# dw8e.net
KiCad netlist of a schematic drawn in EAGLE
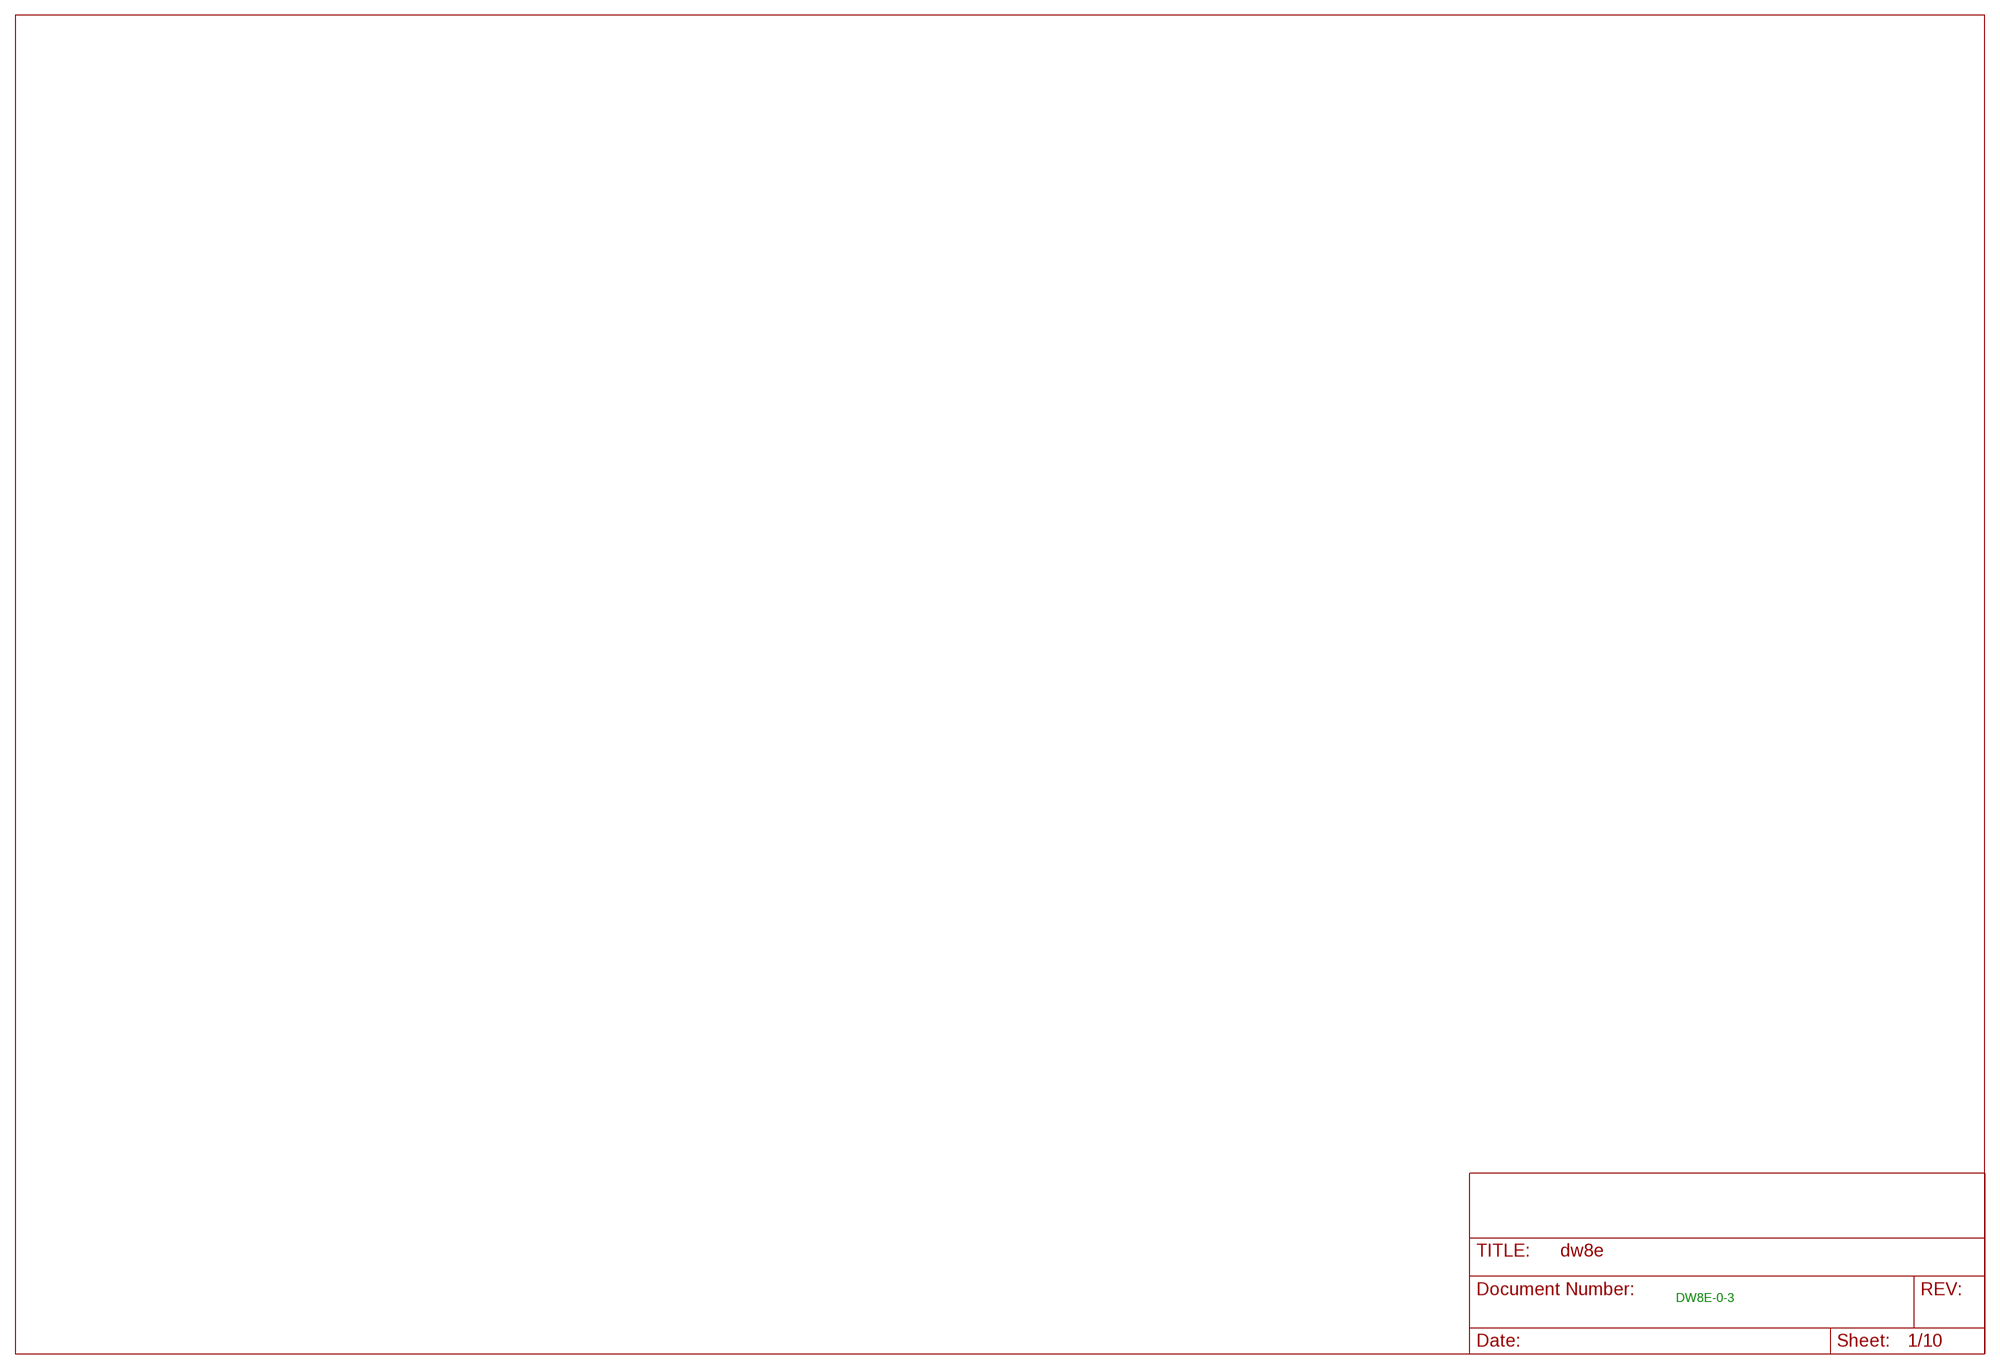
[diagram p0: schematic, sheet 1]
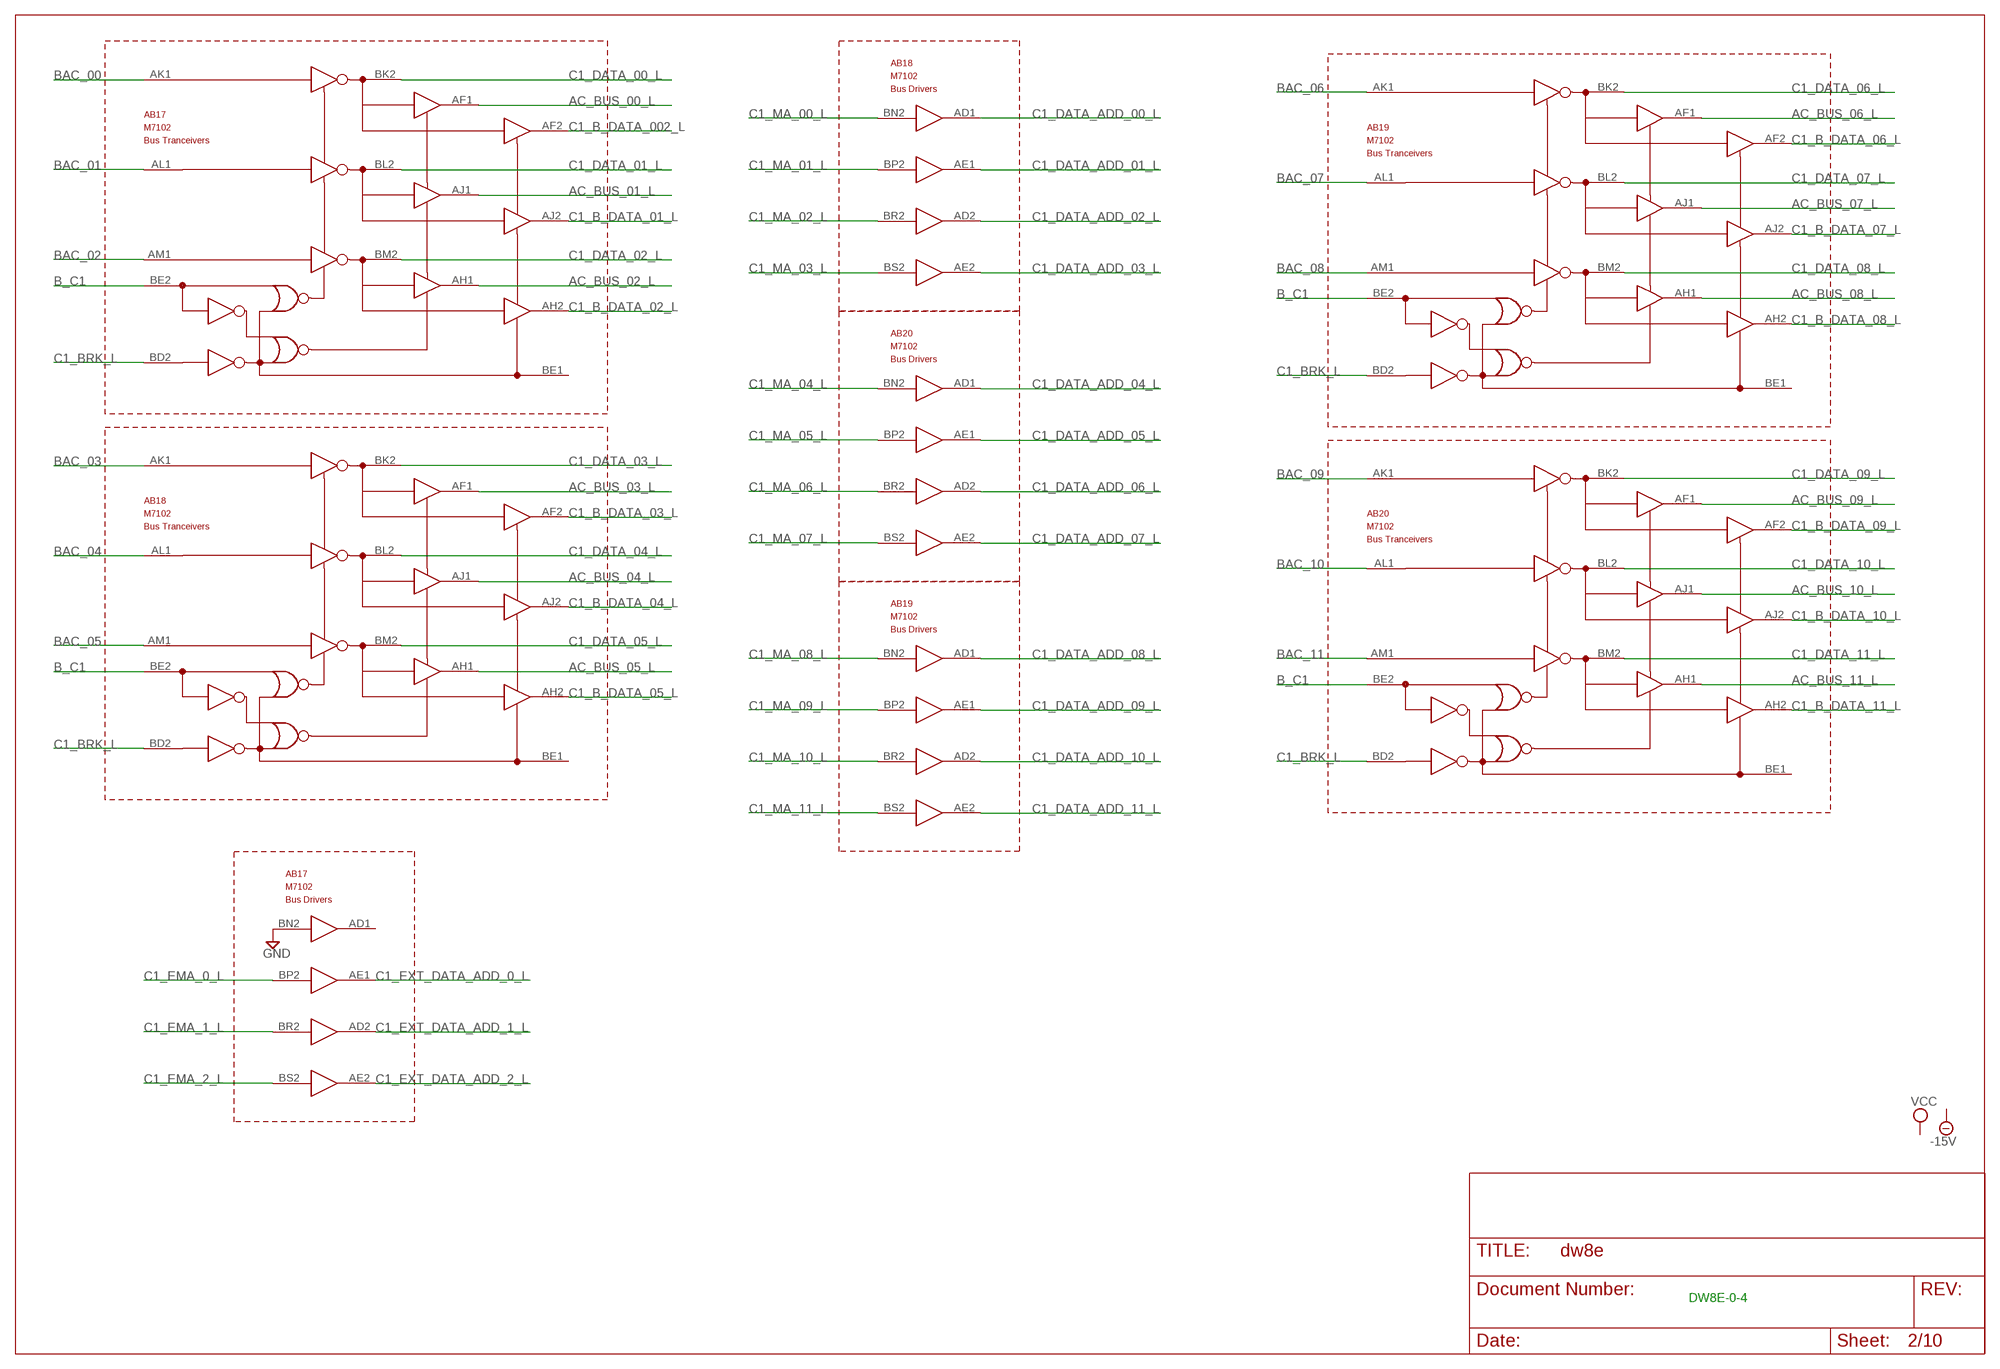
[diagram p1: schematic, sheet 2]
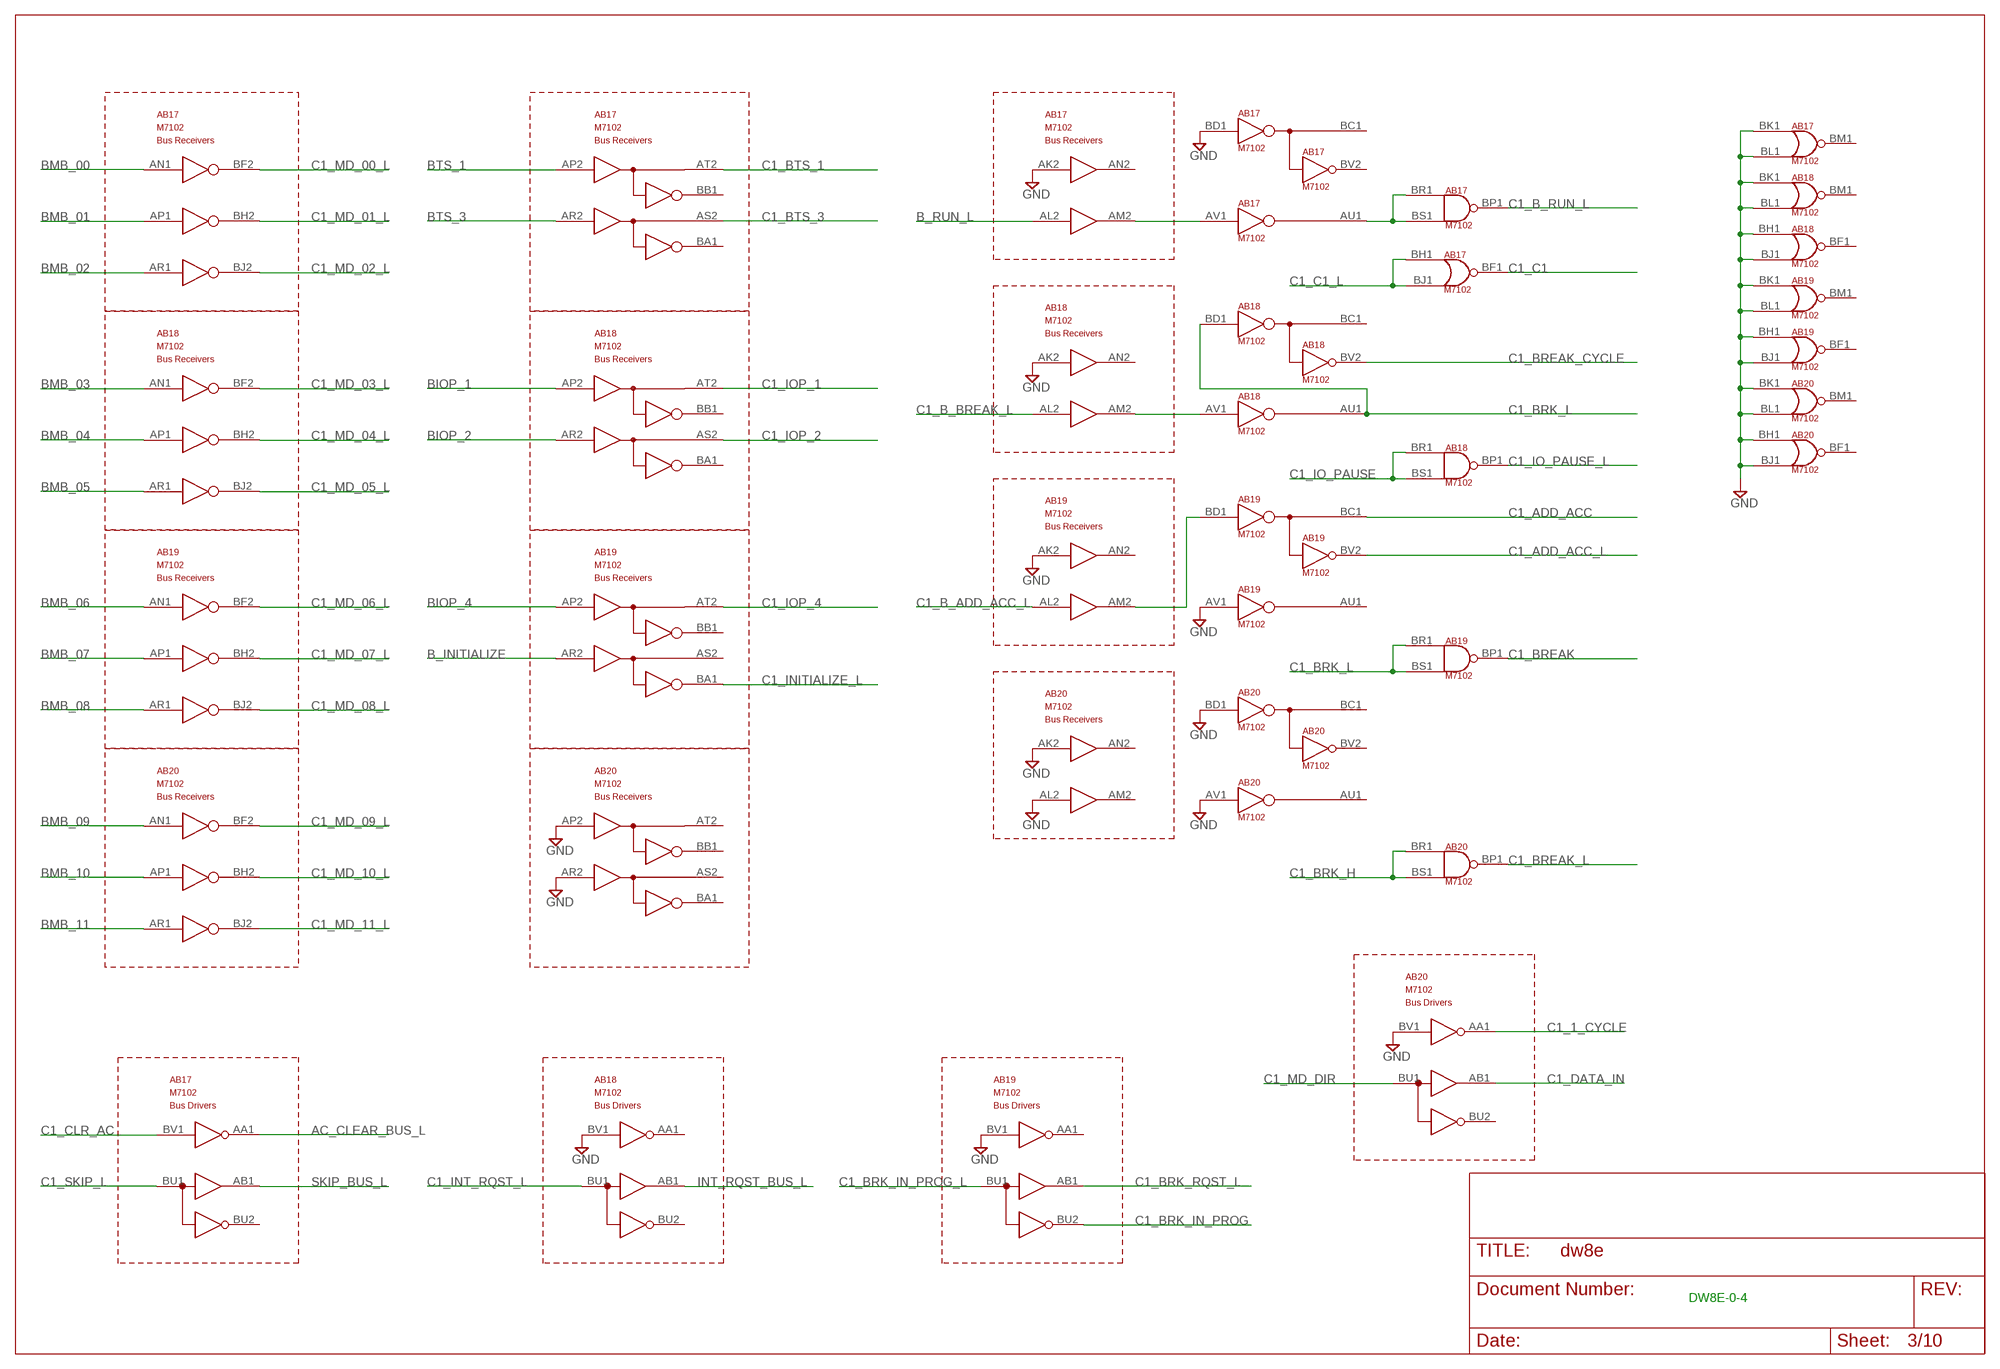
[diagram p2: schematic, sheet 3]
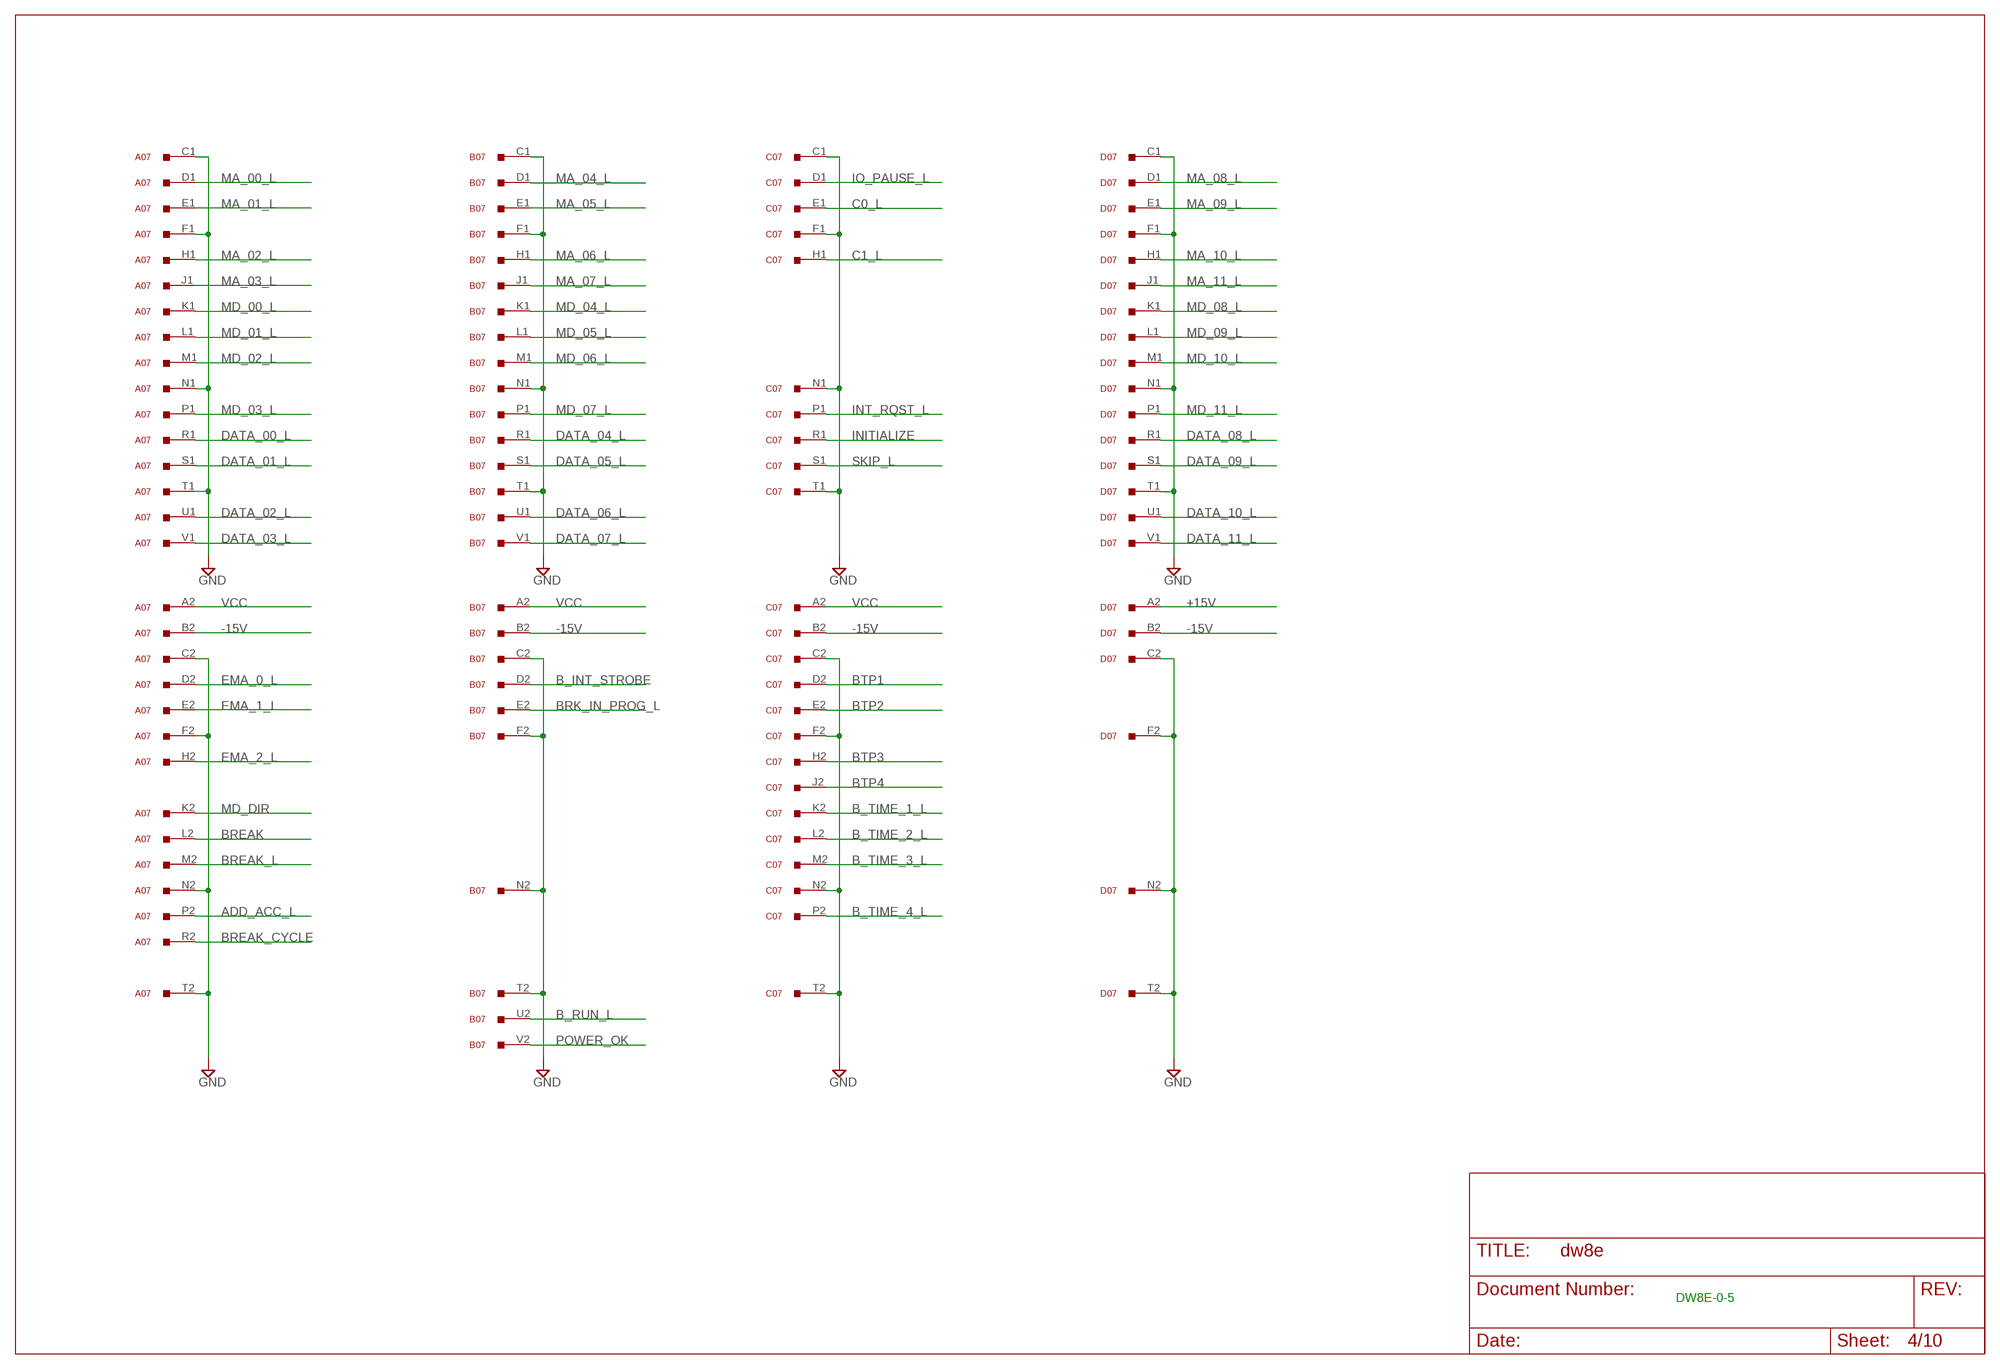
[diagram p3: schematic, sheet 4]
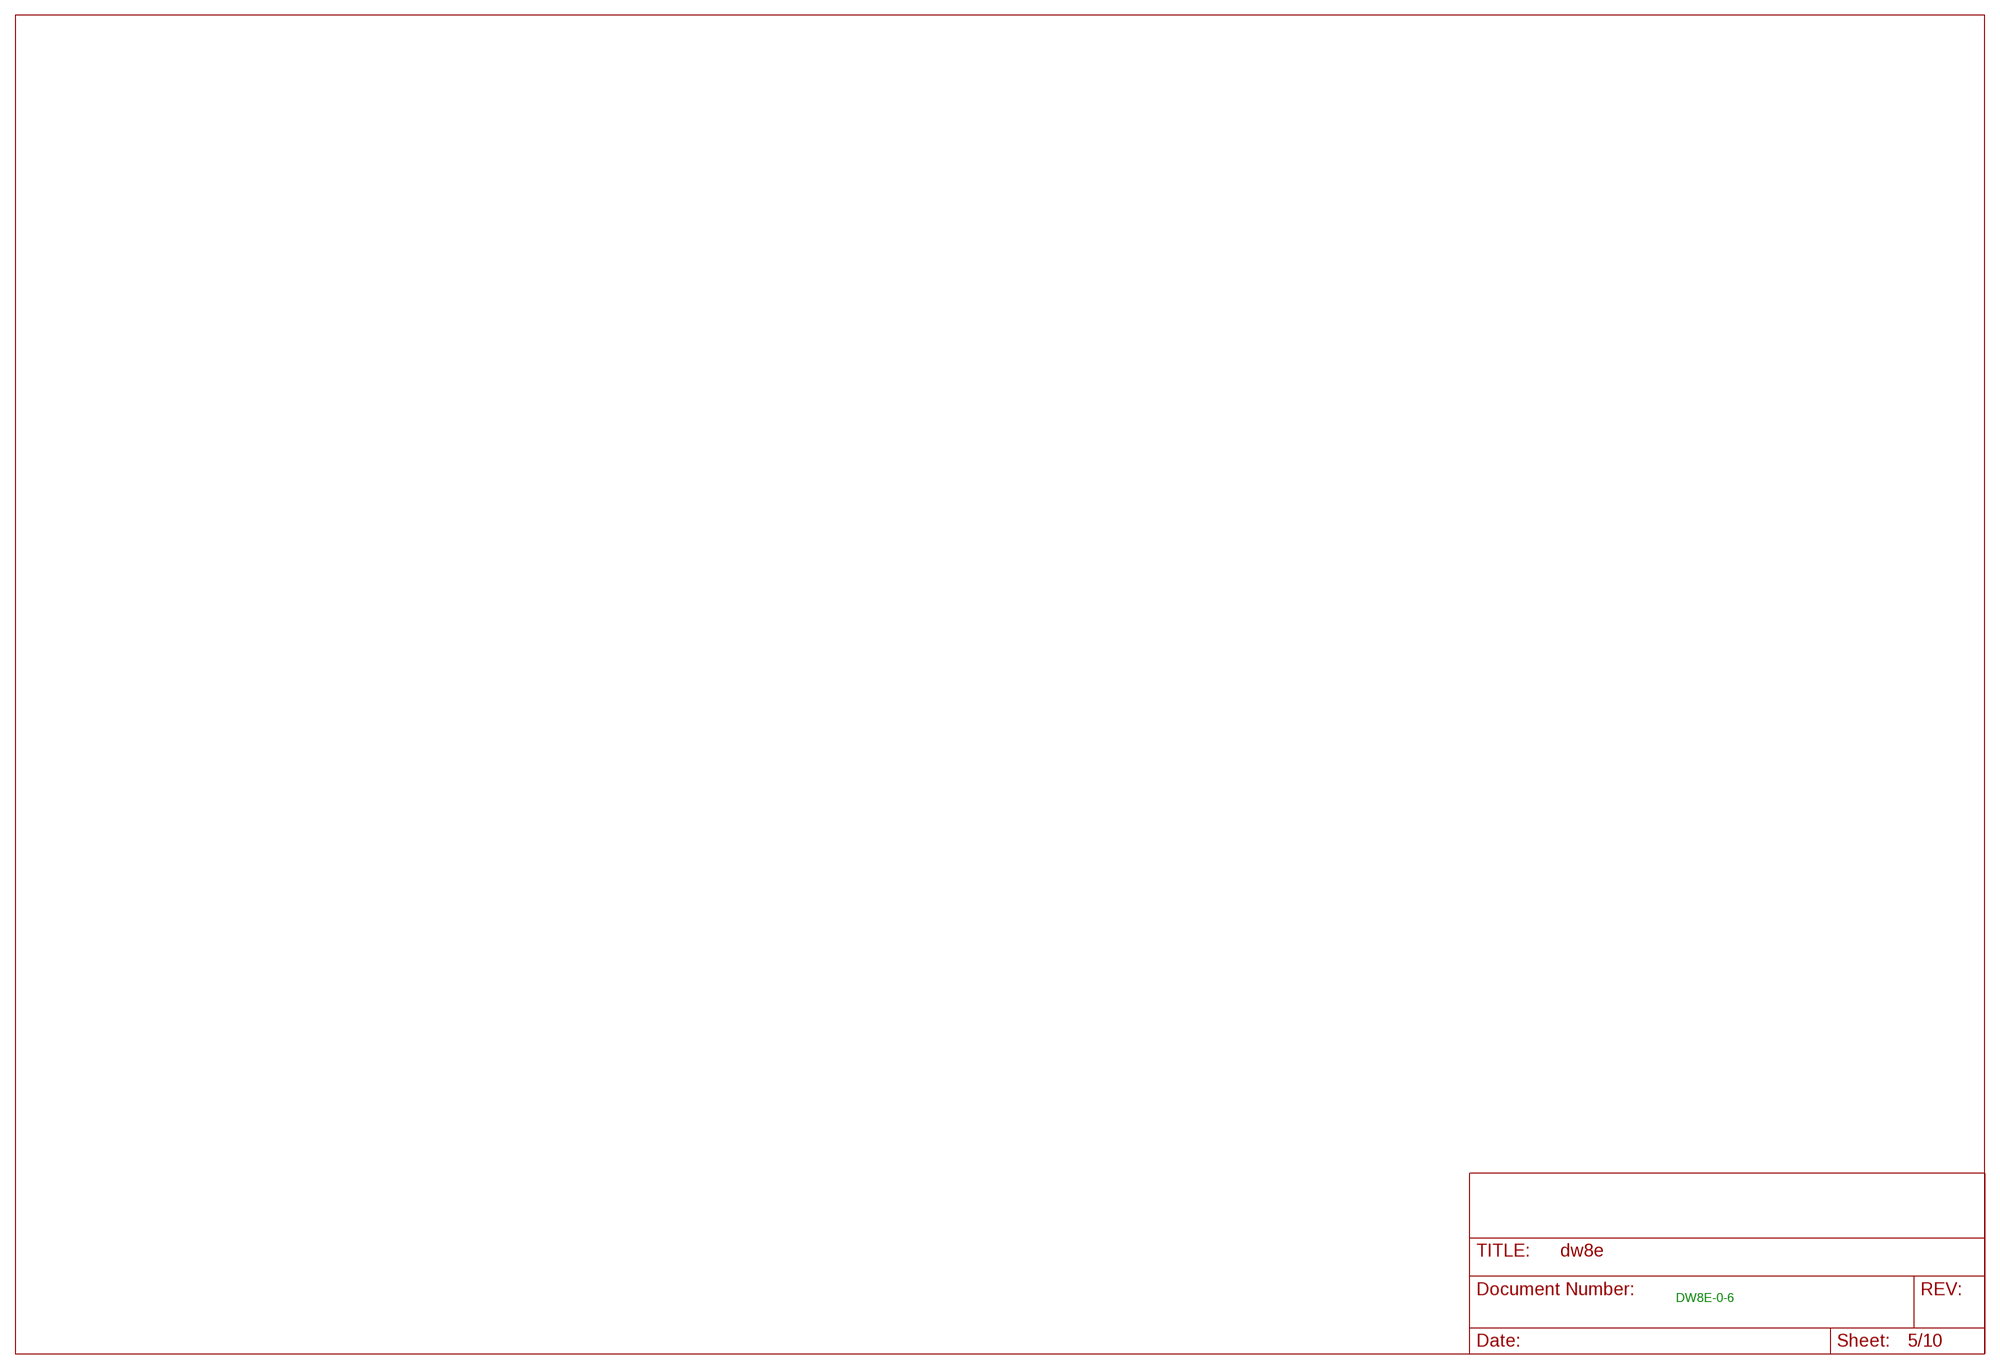
[diagram p4: schematic, sheet 5]
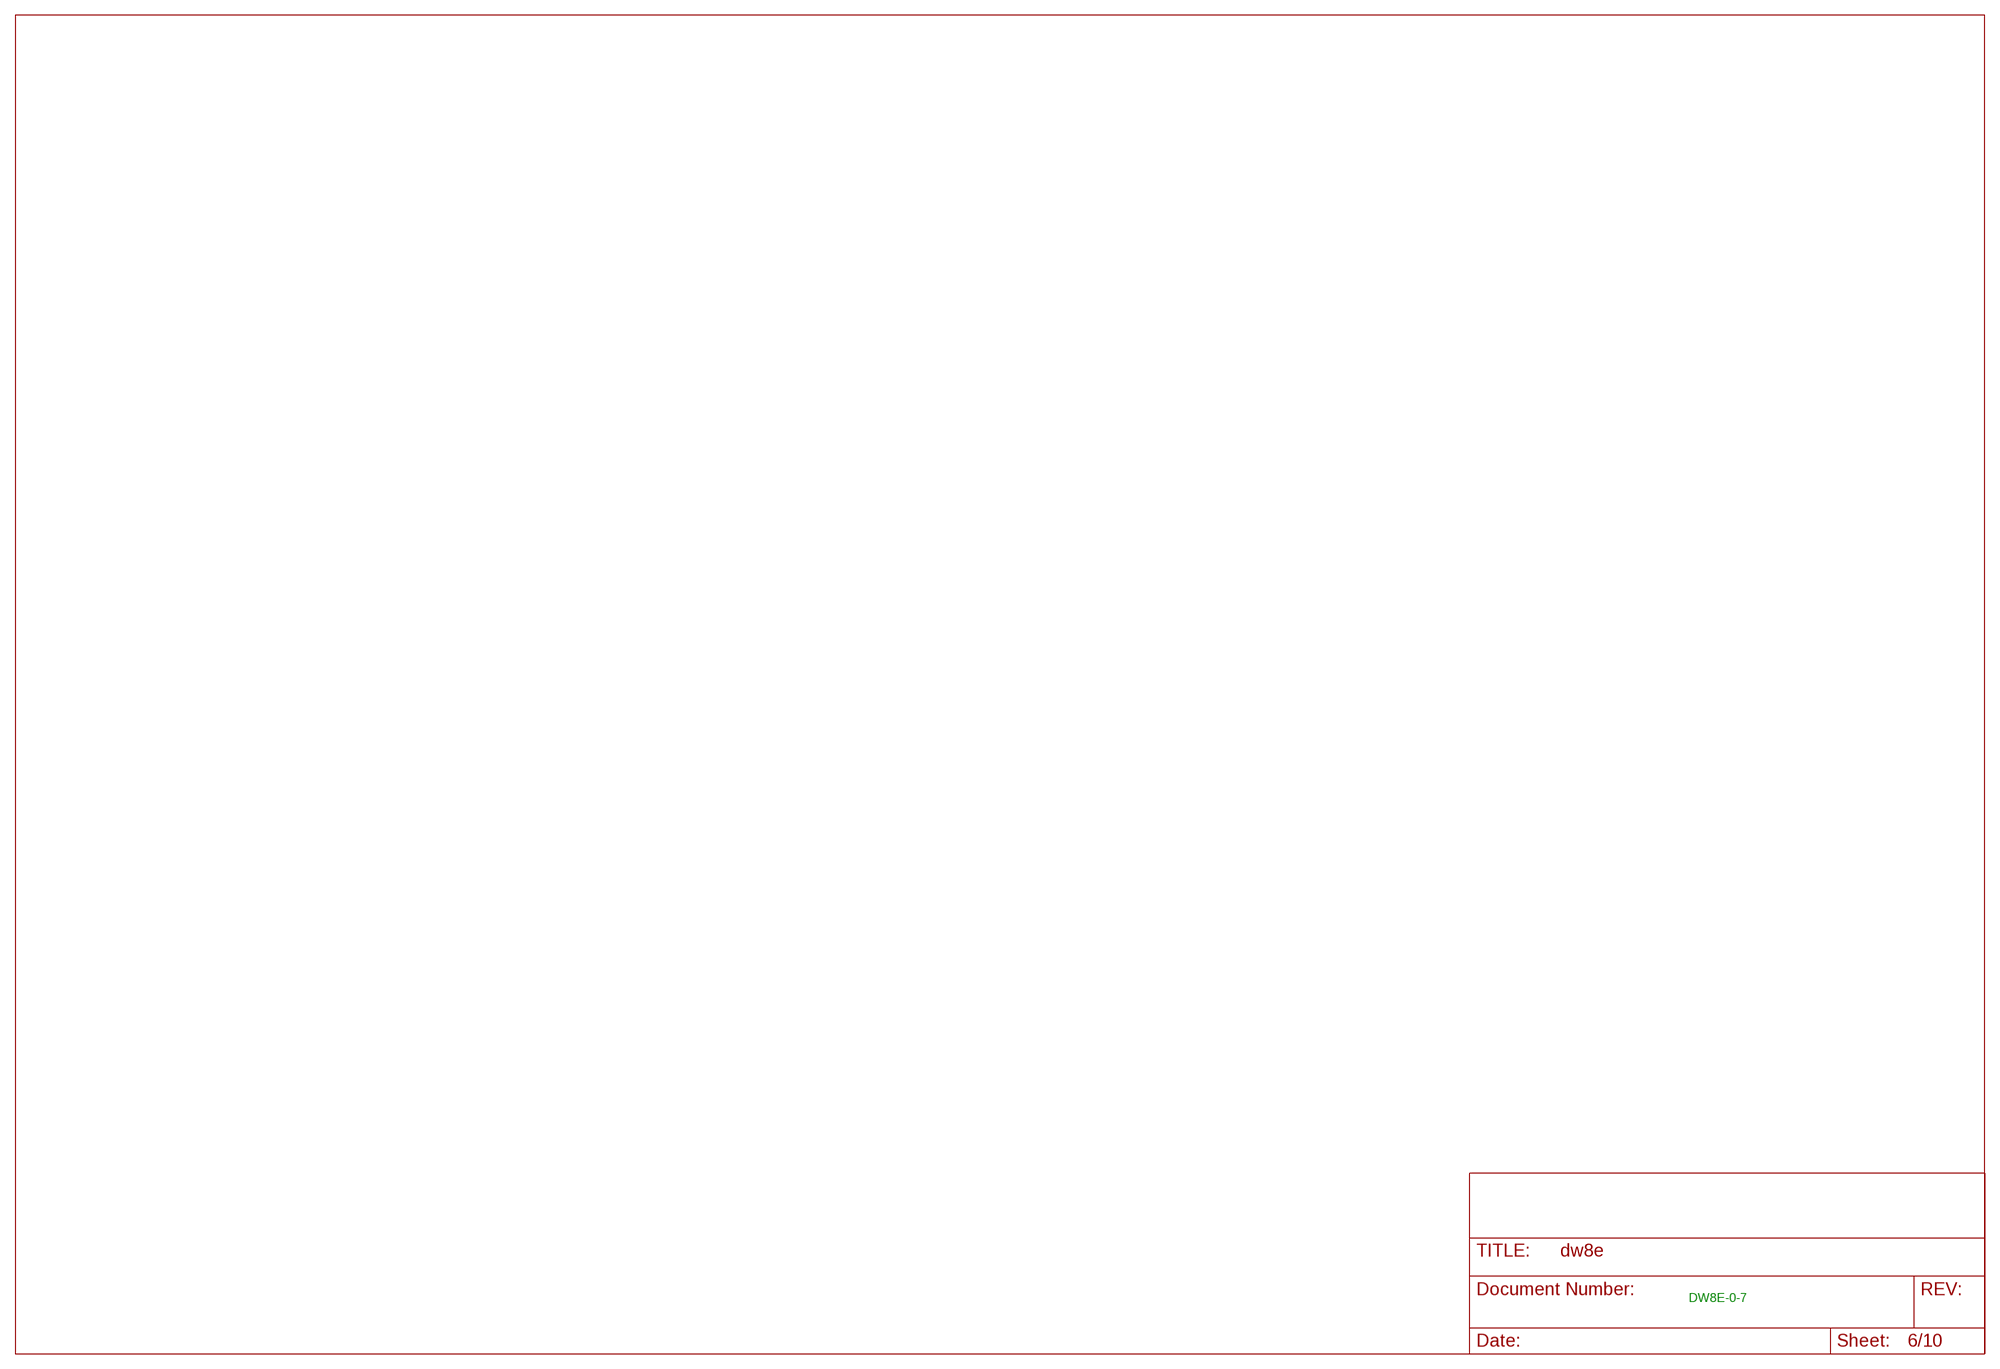
[diagram p5: schematic, sheet 6]
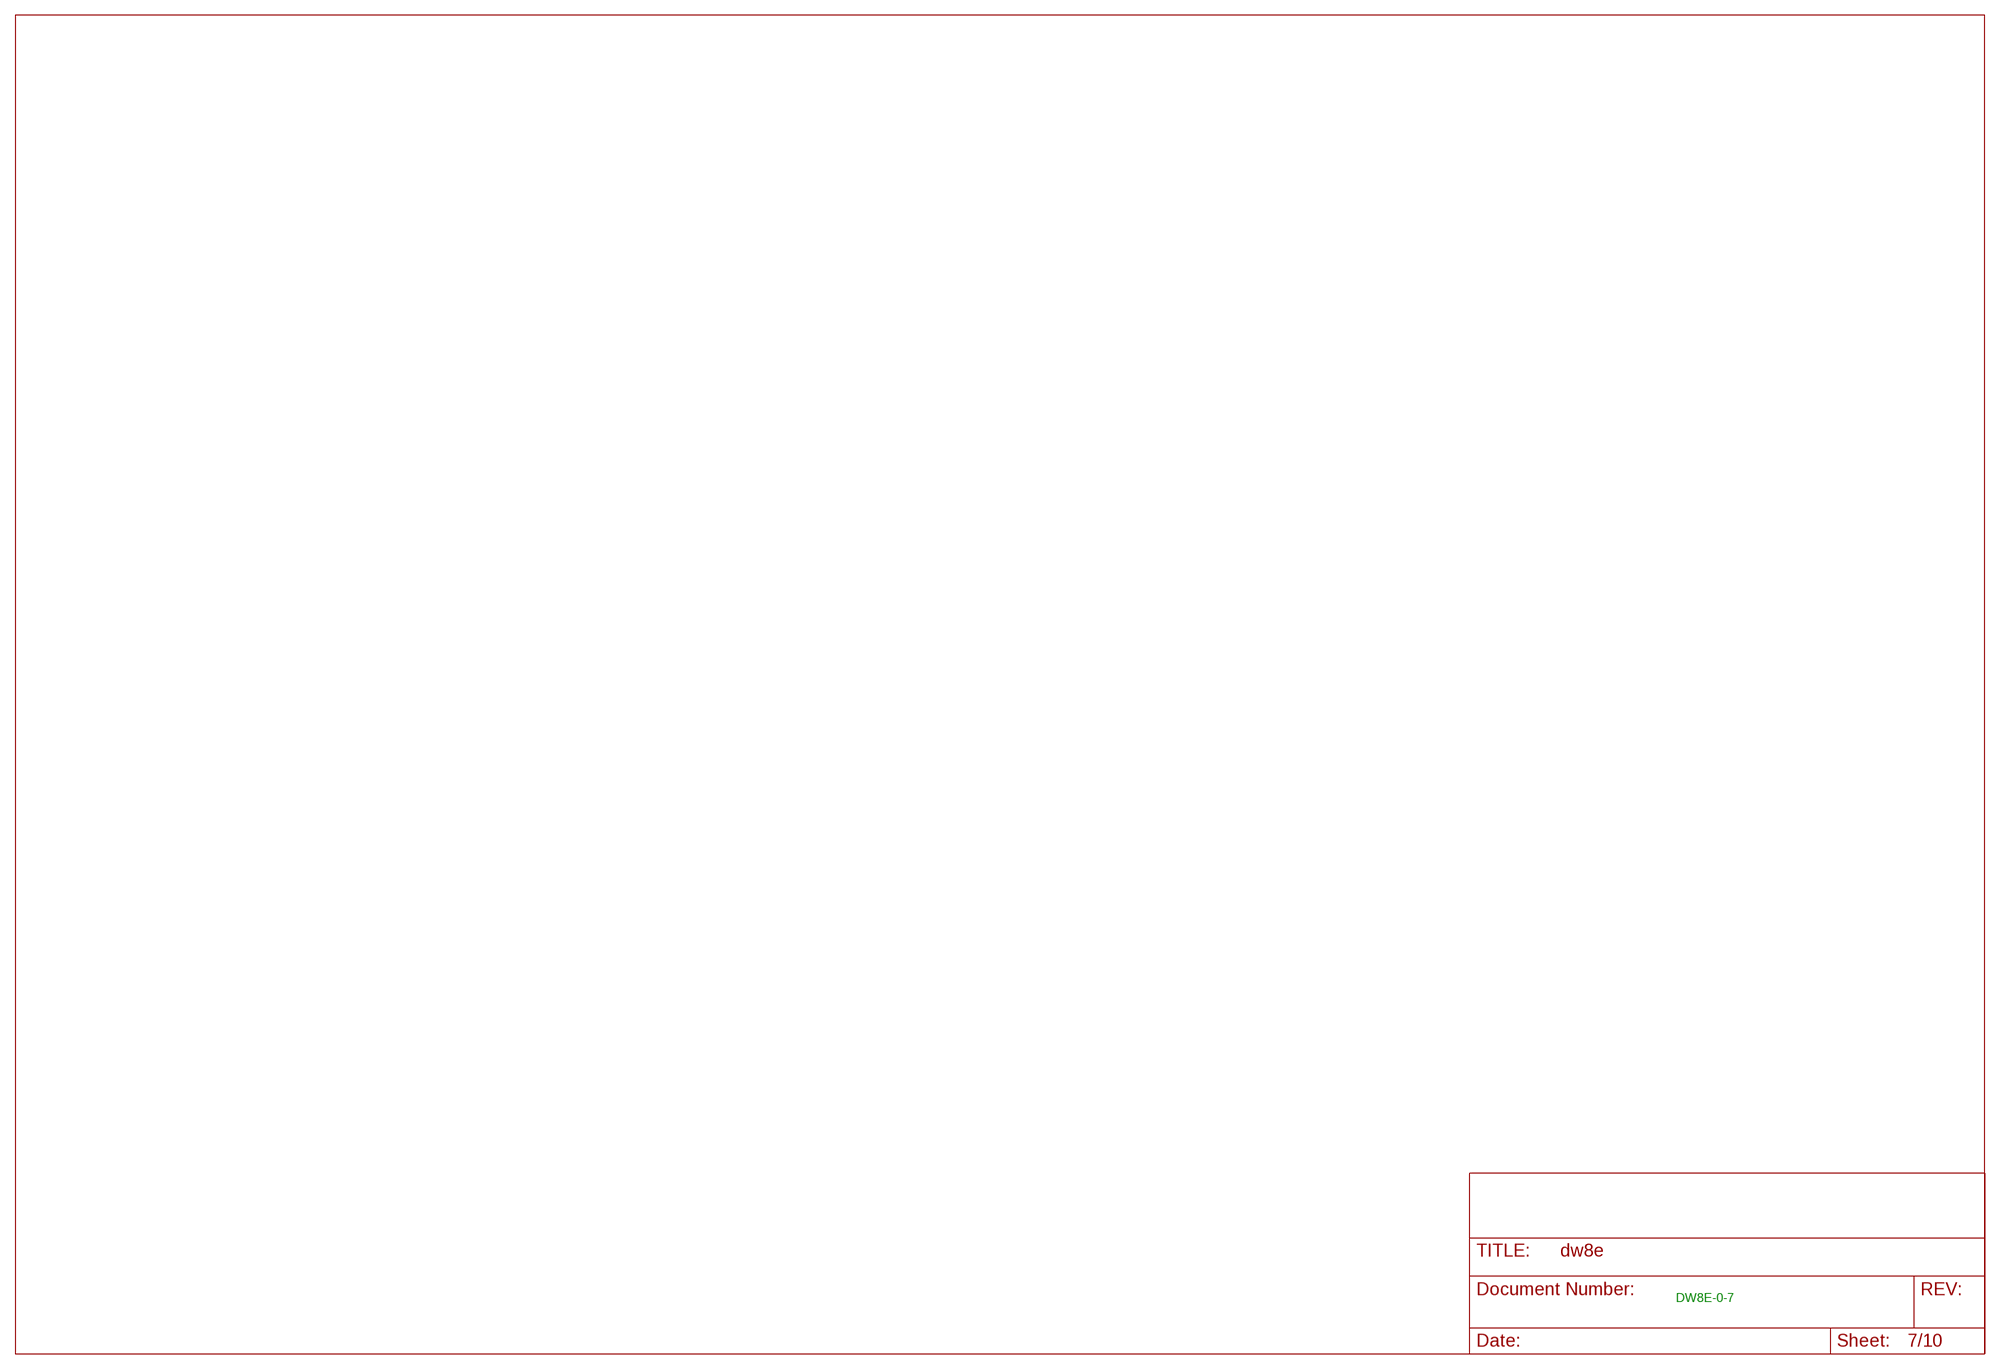
[diagram p6: schematic, sheet 7]
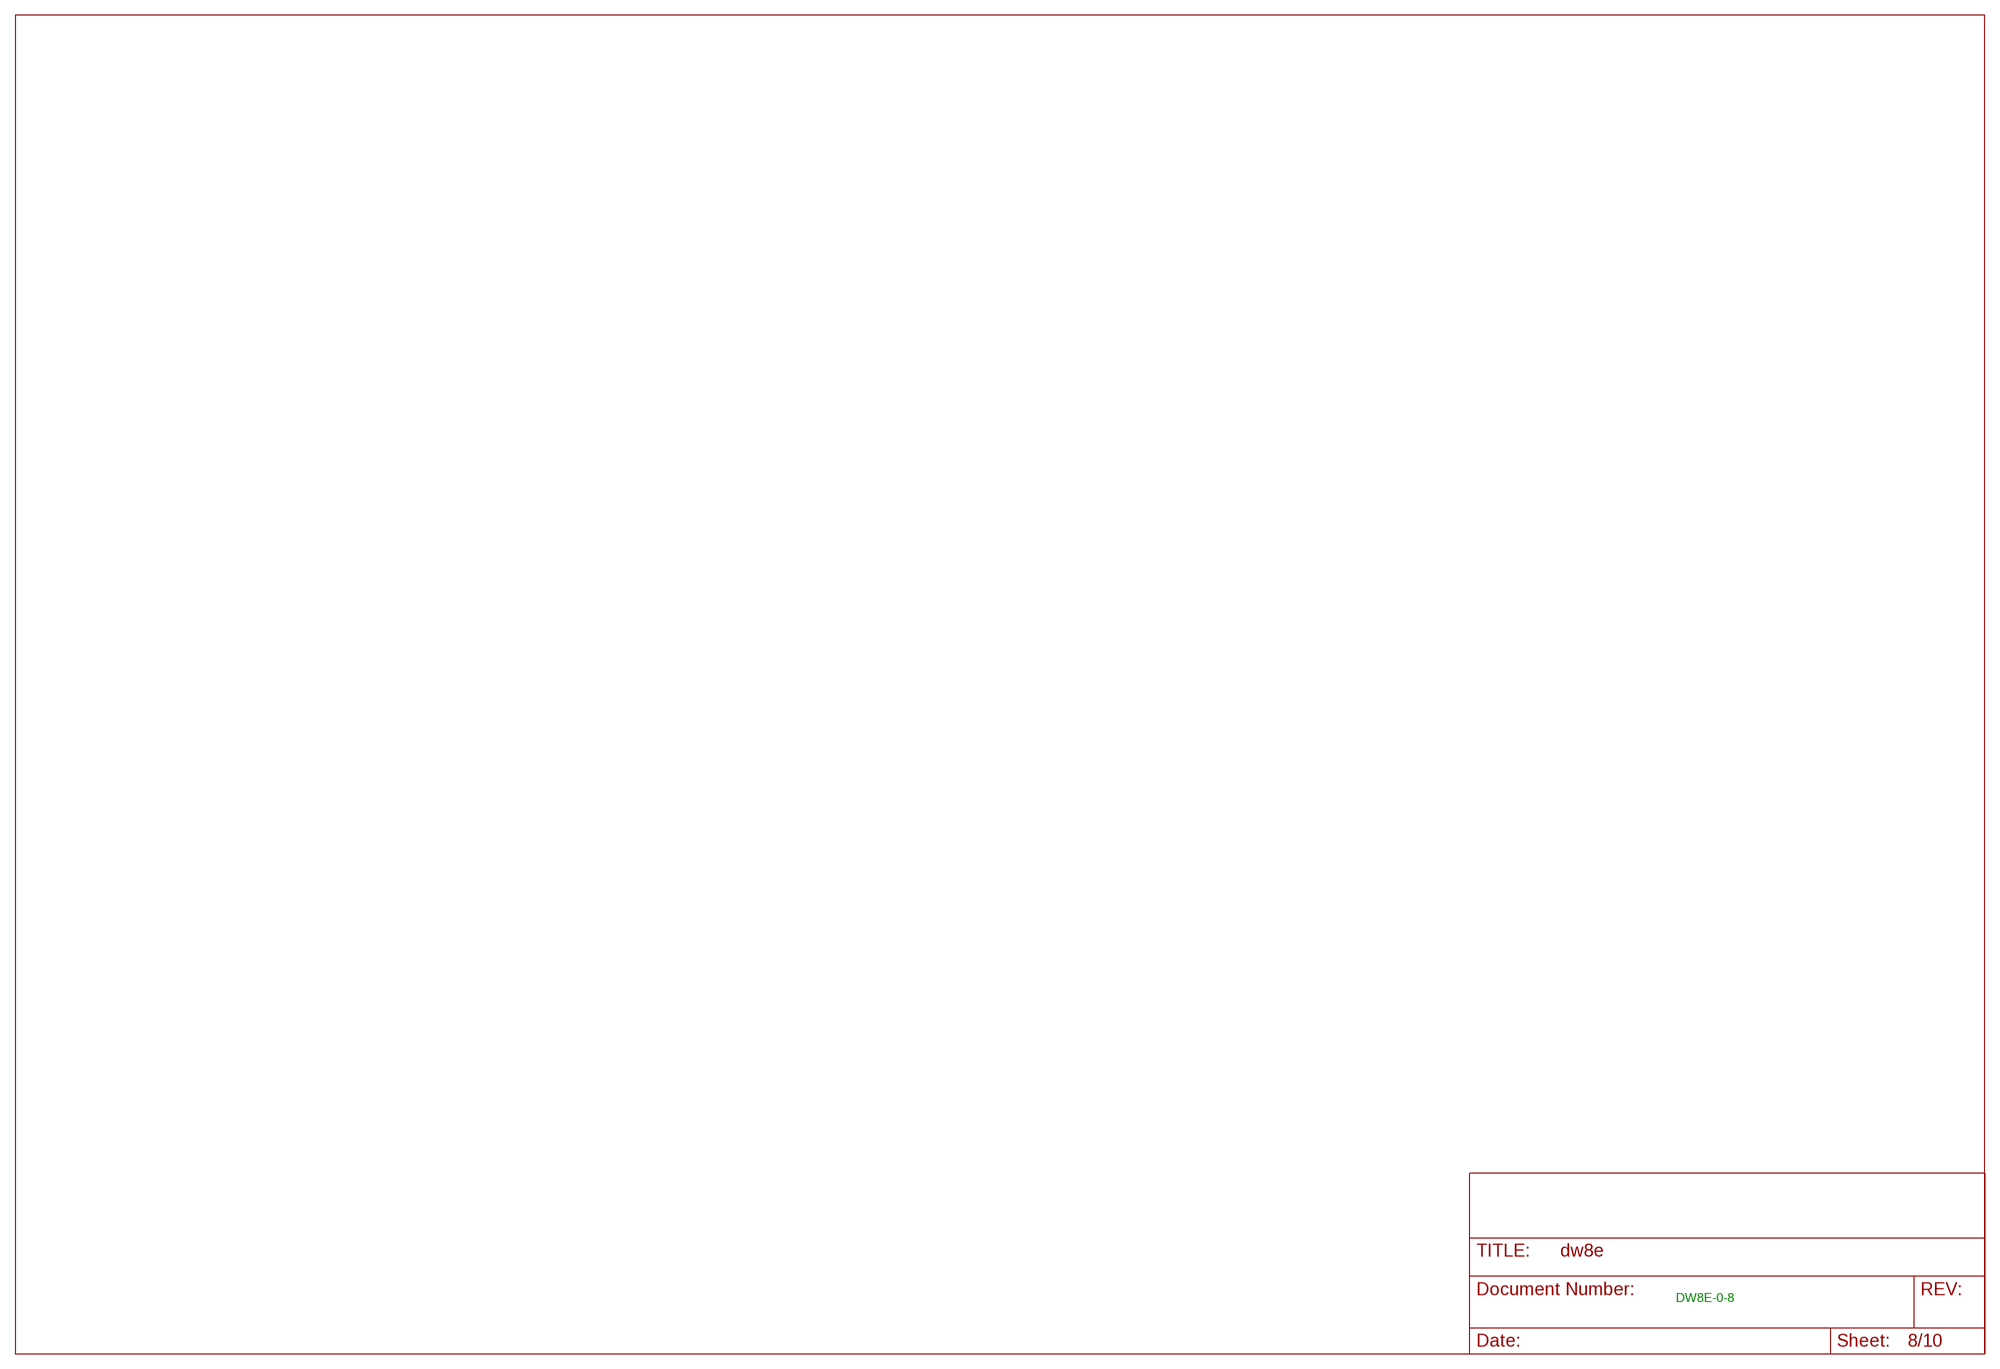
[diagram p7: schematic, sheet 8]
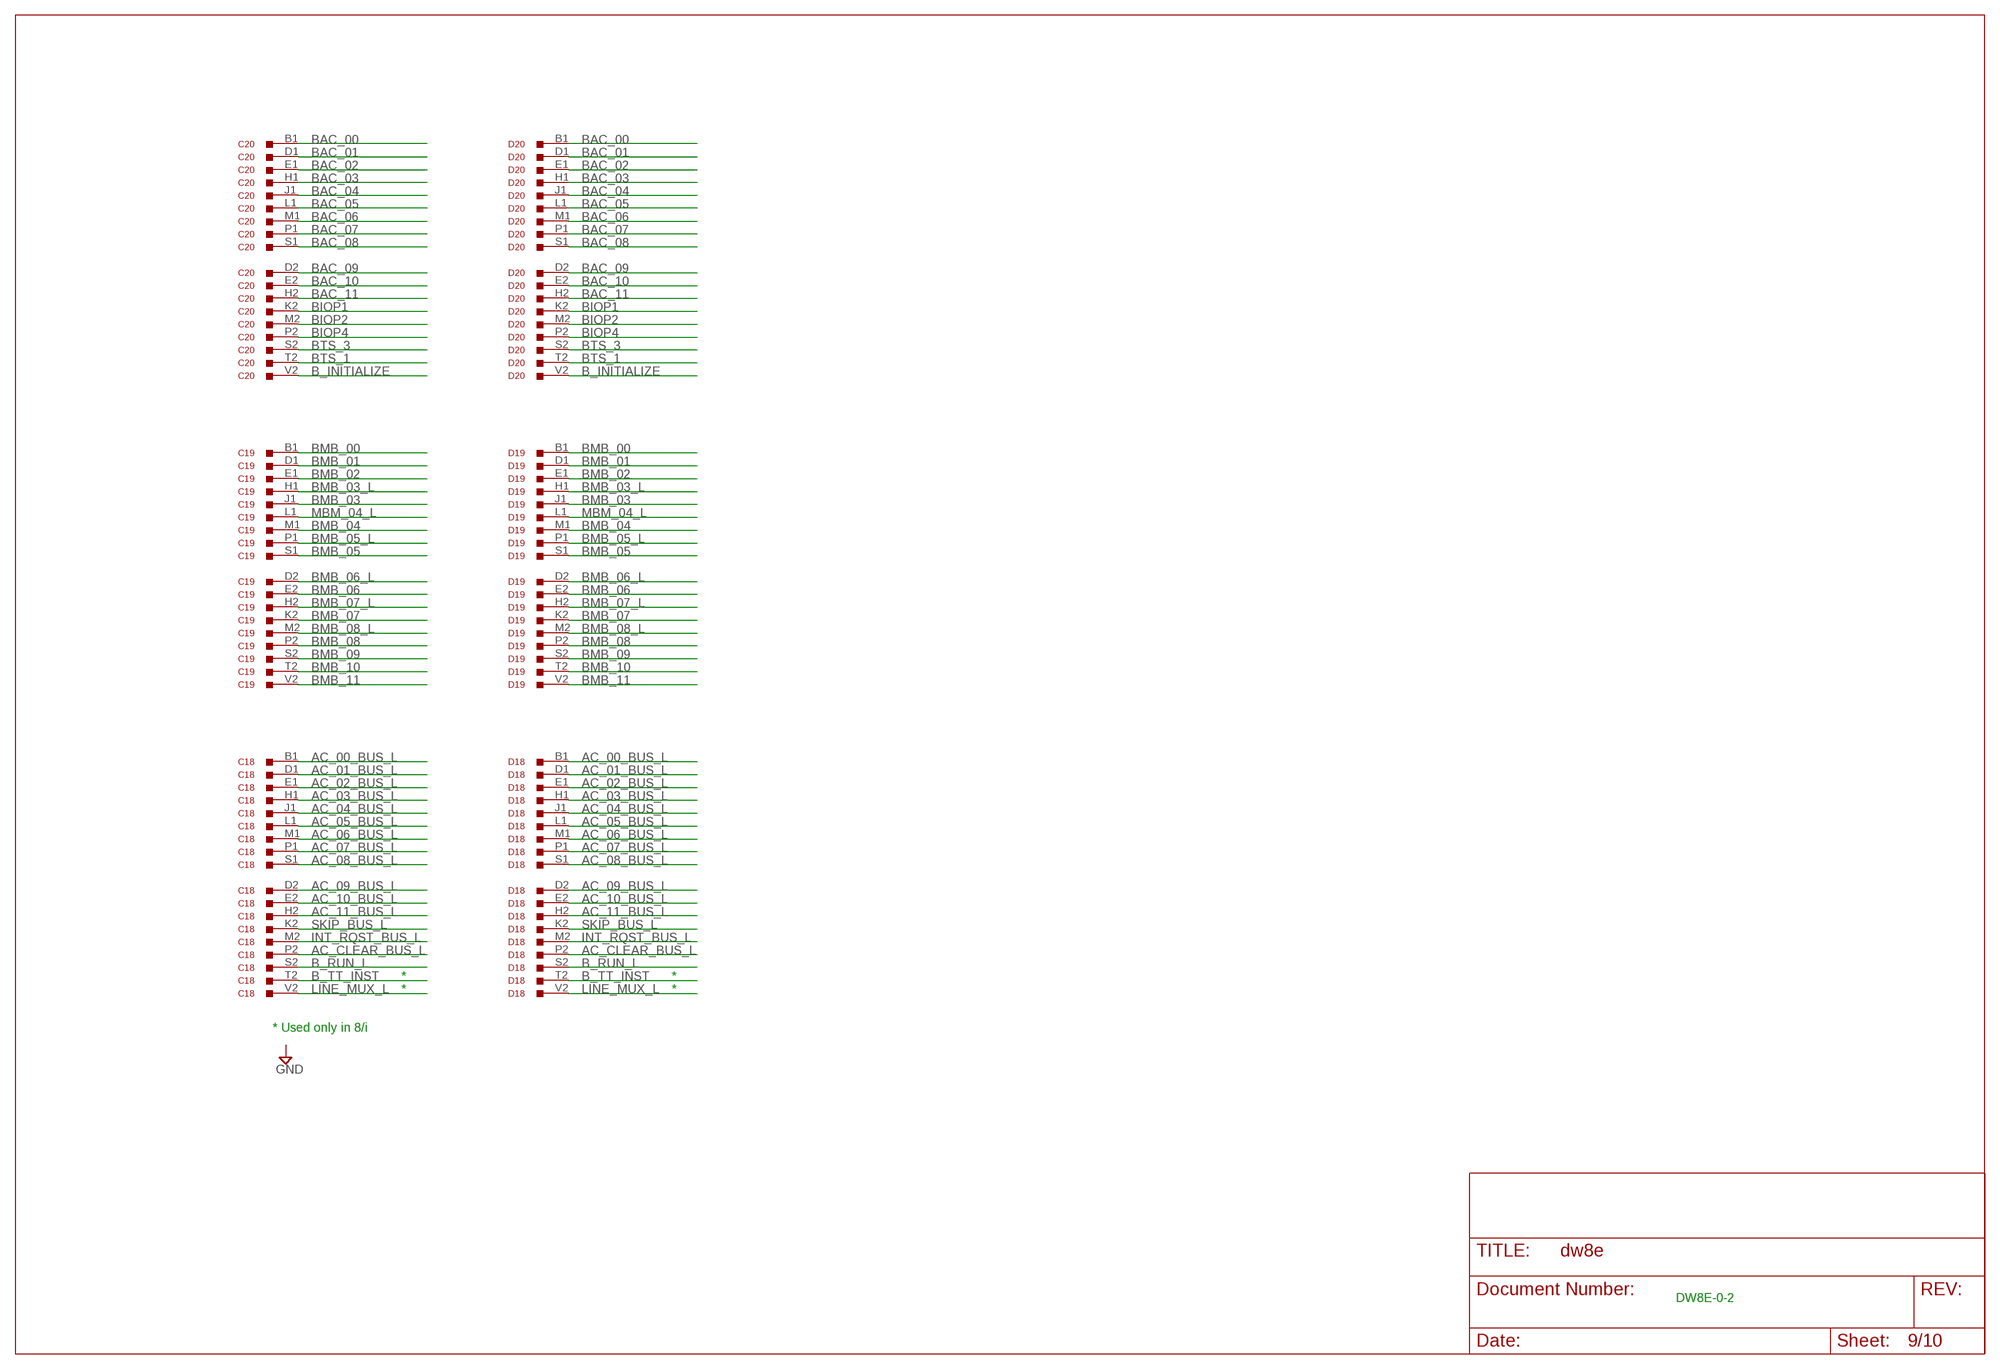
[diagram p8: schematic, sheet 9]
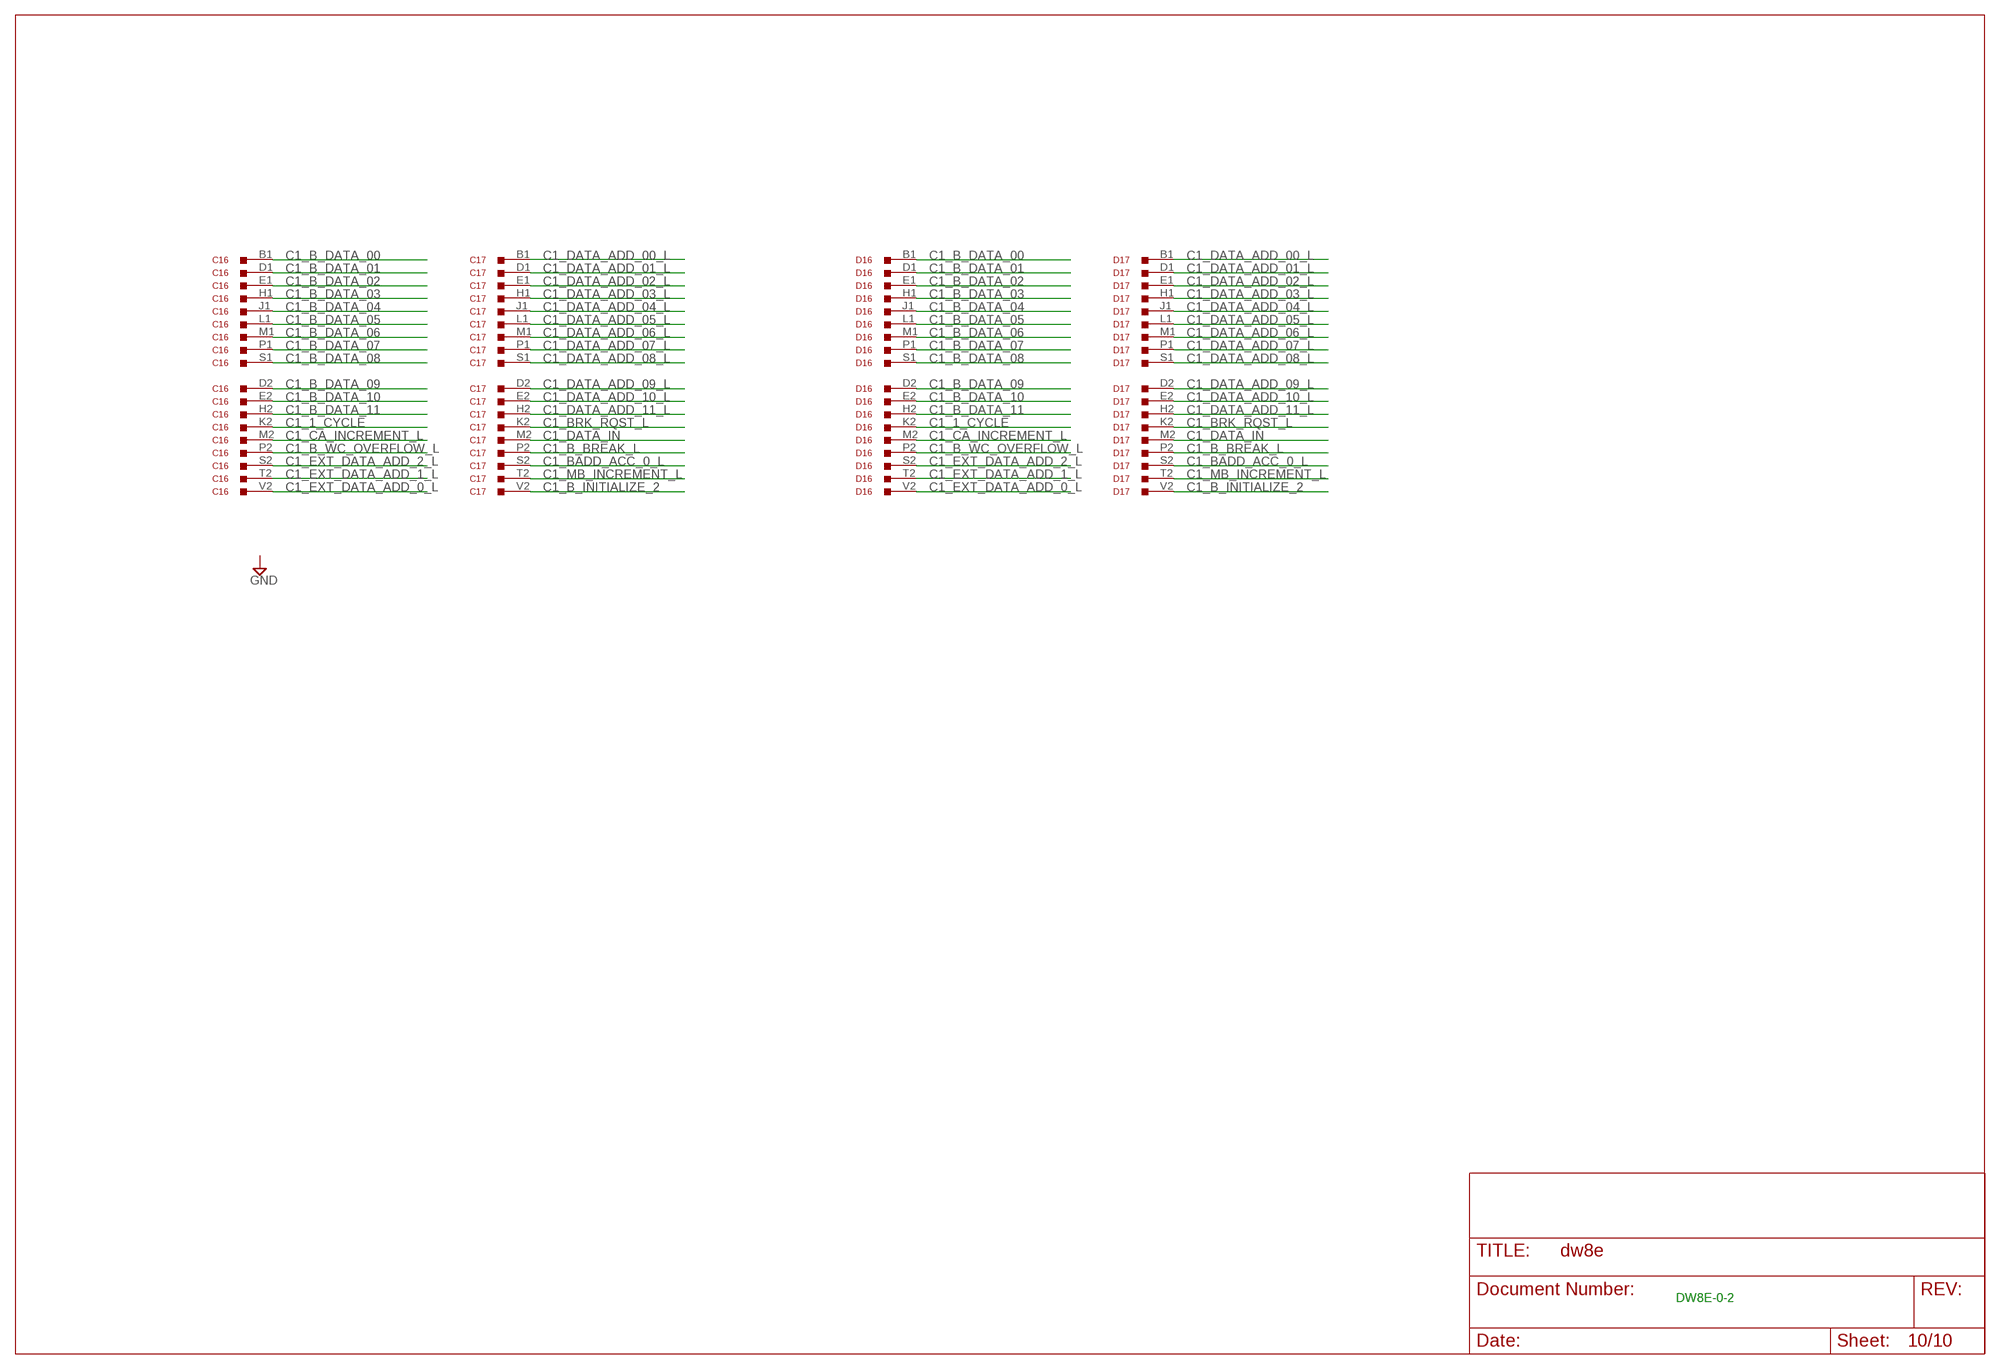
[diagram p9: schematic, sheet 10]

(export (version "E")
  (design (tool "Eeschema 10.0.6"))
  (components
    (comp (ref "A07")
      (value "M916")
      (footprint "eagle-import:H807")
      (libsource (lib "eagle-import") (part "M916"))
    )
    (comp (ref "B07")
      (value "M916")
      (footprint "eagle-import:H807")
      (libsource (lib "eagle-import") (part "M916"))
    )
    (comp (ref "C07")
      (value "M916")
      (footprint "eagle-import:H807")
      (libsource (lib "eagle-import") (part "M916"))
    )
    (comp (ref "D07")
      (value "M916")
      (footprint "eagle-import:H807")
      (libsource (lib "eagle-import") (part "M916"))
    )
    (comp (ref "C16")
      (value "M903")
      (footprint "eagle-import:H807")
      (libsource (lib "eagle-import") (part "M903"))
    )
    (comp (ref "C17")
      (value "M903")
      (footprint "eagle-import:H807")
      (libsource (lib "eagle-import") (part "M903"))
    )
    (comp (ref "D16")
      (value "M903")
      (footprint "eagle-import:H807")
      (libsource (lib "eagle-import") (part "M903"))
    )
    (comp (ref "D17")
      (value "M903")
      (footprint "eagle-import:H807")
      (libsource (lib "eagle-import") (part "M903"))
    )
    (comp (ref "AB17")
      (value "M7102")
      (footprint "eagle-import:H807-2")
      (libsource (lib "eagle-import") (part "M7102"))
    )
    (comp (ref "AB18")
      (value "M7102")
      (footprint "eagle-import:H807-2")
      (libsource (lib "eagle-import") (part "M7102"))
    )
    (comp (ref "AB19")
      (value "M7102")
      (footprint "eagle-import:H807-2")
      (libsource (lib "eagle-import") (part "M7102"))
    )
    (comp (ref "AB20")
      (value "M7102")
      (footprint "eagle-import:H807-2")
      (libsource (lib "eagle-import") (part "M7102"))
    )
    (comp (ref "C18")
      (value "M903")
      (footprint "eagle-import:H807")
      (libsource (lib "eagle-import") (part "M903"))
    )
    (comp (ref "C19")
      (value "M903")
      (footprint "eagle-import:H807")
      (libsource (lib "eagle-import") (part "M903"))
    )
    (comp (ref "C20")
      (value "M903")
      (footprint "eagle-import:H807")
      (libsource (lib "eagle-import") (part "M903"))
    )
    (comp (ref "D18")
      (value "M903")
      (footprint "eagle-import:H807")
      (libsource (lib "eagle-import") (part "M903"))
    )
    (comp (ref "D19")
      (value "M903")
      (footprint "eagle-import:H807")
      (libsource (lib "eagle-import") (part "M903"))
    )
    (comp (ref "D20")
      (value "M903")
      (footprint "eagle-import:H807")
      (libsource (lib "eagle-import") (part "M903"))
    )
  )
  (nets
    (net (code "1") (name "+15V") (class "Default")
      (node (ref "D07") (pin "A2") (pinfunction "P$2_A2") (pintype "bidirectional"))
    )
    (net (code "2") (name "-15V") (class "Default")
      (node (ref "A07") (pin "B2") (pinfunction "P$2_B2") (pintype "bidirectional"))
      (node (ref "B07") (pin "B2") (pinfunction "P$2_B2") (pintype "bidirectional"))
      (node (ref "C07") (pin "B2") (pinfunction "P$2_B2") (pintype "bidirectional"))
      (node (ref "D07") (pin "B2") (pinfunction "P$2_B2") (pintype "bidirectional"))
    )
    (net (code "3") (name "AC_00_BUS_L") (class "Default")
      (node (ref "C18") (pin "B1") (pinfunction "P$2_B1") (pintype "bidirectional"))
      (node (ref "D18") (pin "B1") (pinfunction "P$2_B1") (pintype "bidirectional"))
    )
    (net (code "4") (name "AC_01_BUS_L") (class "Default")
      (node (ref "C18") (pin "D1") (pinfunction "P$2_D1") (pintype "bidirectional"))
      (node (ref "D18") (pin "D1") (pinfunction "P$2_D1") (pintype "bidirectional"))
    )
    (net (code "5") (name "AC_02_BUS_L") (class "Default")
      (node (ref "C18") (pin "E1") (pinfunction "P$2_E1") (pintype "bidirectional"))
      (node (ref "D18") (pin "E1") (pinfunction "P$2_E1") (pintype "bidirectional"))
    )
    (net (code "6") (name "AC_03_BUS_L") (class "Default")
      (node (ref "C18") (pin "H1") (pinfunction "P$2_H1") (pintype "bidirectional"))
      (node (ref "D18") (pin "H1") (pinfunction "P$2_H1") (pintype "bidirectional"))
    )
    (net (code "7") (name "AC_04_BUS_L") (class "Default")
      (node (ref "C18") (pin "J1") (pinfunction "P$2_J1") (pintype "bidirectional"))
      (node (ref "D18") (pin "J1") (pinfunction "P$2_J1") (pintype "bidirectional"))
    )
    (net (code "8") (name "AC_05_BUS_L") (class "Default")
      (node (ref "C18") (pin "L1") (pinfunction "P$2_L1") (pintype "bidirectional"))
      (node (ref "D18") (pin "L1") (pinfunction "P$2_L1") (pintype "bidirectional"))
    )
    (net (code "9") (name "AC_06_BUS_L") (class "Default")
      (node (ref "C18") (pin "M1") (pinfunction "P$2_M1") (pintype "bidirectional"))
      (node (ref "D18") (pin "M1") (pinfunction "P$2_M1") (pintype "bidirectional"))
    )
    (net (code "10") (name "AC_07_BUS_L") (class "Default")
      (node (ref "C18") (pin "P1") (pinfunction "P$2_P1") (pintype "bidirectional"))
      (node (ref "D18") (pin "P1") (pinfunction "P$2_P1") (pintype "bidirectional"))
    )
    (net (code "11") (name "AC_08_BUS_L") (class "Default")
      (node (ref "C18") (pin "S1") (pinfunction "P$2_S1") (pintype "bidirectional"))
      (node (ref "D18") (pin "S1") (pinfunction "P$2_S1") (pintype "bidirectional"))
    )
    (net (code "12") (name "AC_09_BUS_L") (class "Default")
      (node (ref "C18") (pin "D2") (pinfunction "P$2_D2") (pintype "bidirectional"))
      (node (ref "D18") (pin "D2") (pinfunction "P$2_D2") (pintype "bidirectional"))
    )
    (net (code "13") (name "AC_10_BUS_L") (class "Default")
      (node (ref "C18") (pin "E2") (pinfunction "P$2_E2") (pintype "bidirectional"))
      (node (ref "D18") (pin "E2") (pinfunction "P$2_E2") (pintype "bidirectional"))
    )
    (net (code "14") (name "AC_11_BUS_L") (class "Default")
      (node (ref "C18") (pin "H2") (pinfunction "P$2_H2") (pintype "bidirectional"))
      (node (ref "D18") (pin "H2") (pinfunction "P$2_H2") (pintype "bidirectional"))
    )
    (net (code "15") (name "AC_BUS_00_L") (class "Default")
      (node (ref "AB17") (pin "AF1") (pinfunction "AF1_AF1") (pintype "open_collector"))
    )
    (net (code "16") (name "AC_BUS_01_L") (class "Default")
      (node (ref "AB17") (pin "AJ1") (pinfunction "AJ1_AJ1") (pintype "open_collector"))
    )
    (net (code "17") (name "AC_BUS_02_L") (class "Default")
      (node (ref "AB17") (pin "AH1") (pinfunction "AH1_AH1") (pintype "open_collector"))
    )
    (net (code "18") (name "AC_BUS_03_L") (class "Default")
      (node (ref "AB18") (pin "AF1") (pinfunction "AF1_AF1") (pintype "open_collector"))
    )
    (net (code "19") (name "AC_BUS_04_L") (class "Default")
      (node (ref "AB18") (pin "AJ1") (pinfunction "AJ1_AJ1") (pintype "open_collector"))
    )
    (net (code "20") (name "AC_BUS_05_L") (class "Default")
      (node (ref "AB18") (pin "AH1") (pinfunction "AH1_AH1") (pintype "open_collector"))
    )
    (net (code "21") (name "AC_BUS_06_L") (class "Default")
      (node (ref "AB19") (pin "AF1") (pinfunction "AF1_AF1") (pintype "open_collector"))
    )
    (net (code "22") (name "AC_BUS_07_L") (class "Default")
      (node (ref "AB19") (pin "AJ1") (pinfunction "AJ1_AJ1") (pintype "open_collector"))
    )
    (net (code "23") (name "AC_BUS_08_L") (class "Default")
      (node (ref "AB19") (pin "AH1") (pinfunction "AH1_AH1") (pintype "open_collector"))
    )
    (net (code "24") (name "AC_BUS_09_L") (class "Default")
      (node (ref "AB20") (pin "AF1") (pinfunction "AF1_AF1") (pintype "open_collector"))
    )
    (net (code "25") (name "AC_BUS_10_L") (class "Default")
      (node (ref "AB20") (pin "AJ1") (pinfunction "AJ1_AJ1") (pintype "open_collector"))
    )
    (net (code "26") (name "AC_BUS_11_L") (class "Default")
      (node (ref "AB20") (pin "AH1") (pinfunction "AH1_AH1") (pintype "open_collector"))
    )
    (net (code "27") (name "AC_CLEAR_BUS_L") (class "Default")
      (node (ref "AB17") (pin "AA1") (pinfunction "AA1_AA1") (pintype "open_collector"))
      (node (ref "C18") (pin "P2") (pinfunction "P$2_P2") (pintype "bidirectional"))
      (node (ref "D18") (pin "P2") (pinfunction "P$2_P2") (pintype "bidirectional"))
    )
    (net (code "28") (name "ADD_ACC_L") (class "Default")
      (node (ref "A07") (pin "P2") (pinfunction "P$2_P2") (pintype "bidirectional"))
    )
    (net (code "29") (name "BAC_00") (class "Default")
      (node (ref "AB17") (pin "AK1") (pinfunction "AK1_AK1") (pintype "input"))
      (node (ref "C20") (pin "B1") (pinfunction "P$2_B1") (pintype "bidirectional"))
      (node (ref "D20") (pin "B1") (pinfunction "P$2_B1") (pintype "bidirectional"))
    )
    (net (code "30") (name "BAC_01") (class "Default")
      (node (ref "AB17") (pin "AL1") (pinfunction "AL1_AL1") (pintype "input"))
      (node (ref "C20") (pin "D1") (pinfunction "P$2_D1") (pintype "bidirectional"))
      (node (ref "D20") (pin "D1") (pinfunction "P$2_D1") (pintype "bidirectional"))
    )
    (net (code "31") (name "BAC_02") (class "Default")
      (node (ref "AB17") (pin "AM1") (pinfunction "AM1_AM1") (pintype "input"))
      (node (ref "C20") (pin "E1") (pinfunction "P$2_E1") (pintype "bidirectional"))
      (node (ref "D20") (pin "E1") (pinfunction "P$2_E1") (pintype "bidirectional"))
    )
    (net (code "32") (name "BAC_03") (class "Default")
      (node (ref "AB18") (pin "AK1") (pinfunction "AK1_AK1") (pintype "input"))
      (node (ref "C20") (pin "H1") (pinfunction "P$2_H1") (pintype "bidirectional"))
      (node (ref "D20") (pin "H1") (pinfunction "P$2_H1") (pintype "bidirectional"))
    )
    (net (code "33") (name "BAC_04") (class "Default")
      (node (ref "AB18") (pin "AL1") (pinfunction "AL1_AL1") (pintype "input"))
      (node (ref "C20") (pin "J1") (pinfunction "P$2_J1") (pintype "bidirectional"))
      (node (ref "D20") (pin "J1") (pinfunction "P$2_J1") (pintype "bidirectional"))
    )
    (net (code "34") (name "BAC_05") (class "Default")
      (node (ref "AB18") (pin "AM1") (pinfunction "AM1_AM1") (pintype "input"))
      (node (ref "C20") (pin "L1") (pinfunction "P$2_L1") (pintype "bidirectional"))
      (node (ref "D20") (pin "L1") (pinfunction "P$2_L1") (pintype "bidirectional"))
    )
    (net (code "35") (name "BAC_06") (class "Default")
      (node (ref "AB19") (pin "AK1") (pinfunction "AK1_AK1") (pintype "input"))
      (node (ref "C20") (pin "M1") (pinfunction "P$2_M1") (pintype "bidirectional"))
      (node (ref "D20") (pin "M1") (pinfunction "P$2_M1") (pintype "bidirectional"))
    )
    (net (code "36") (name "BAC_07") (class "Default")
      (node (ref "AB19") (pin "AL1") (pinfunction "AL1_AL1") (pintype "input"))
      (node (ref "C20") (pin "P1") (pinfunction "P$2_P1") (pintype "bidirectional"))
      (node (ref "D20") (pin "P1") (pinfunction "P$2_P1") (pintype "bidirectional"))
    )
    (net (code "37") (name "BAC_08") (class "Default")
      (node (ref "AB19") (pin "AM1") (pinfunction "AM1_AM1") (pintype "input"))
      (node (ref "C20") (pin "S1") (pinfunction "P$2_S1") (pintype "bidirectional"))
      (node (ref "D20") (pin "S1") (pinfunction "P$2_S1") (pintype "bidirectional"))
    )
    (net (code "38") (name "BAC_09") (class "Default")
      (node (ref "AB20") (pin "AK1") (pinfunction "AK1_AK1") (pintype "input"))
      (node (ref "C20") (pin "D2") (pinfunction "P$2_D2") (pintype "bidirectional"))
      (node (ref "D20") (pin "D2") (pinfunction "P$2_D2") (pintype "bidirectional"))
    )
    (net (code "39") (name "BAC_10") (class "Default")
      (node (ref "AB20") (pin "AL1") (pinfunction "AL1_AL1") (pintype "input"))
      (node (ref "C20") (pin "E2") (pinfunction "P$2_E2") (pintype "bidirectional"))
      (node (ref "D20") (pin "E2") (pinfunction "P$2_E2") (pintype "bidirectional"))
    )
    (net (code "40") (name "BAC_11") (class "Default")
      (node (ref "AB20") (pin "AM1") (pinfunction "AM1_AM1") (pintype "input"))
      (node (ref "C20") (pin "H2") (pinfunction "P$2_H2") (pintype "bidirectional"))
      (node (ref "D20") (pin "H2") (pinfunction "P$2_H2") (pintype "bidirectional"))
    )
    (net (code "41") (name "BIOP1") (class "Default")
      (node (ref "C20") (pin "K2") (pinfunction "P$2_K2") (pintype "bidirectional"))
      (node (ref "D20") (pin "K2") (pinfunction "P$2_K2") (pintype "bidirectional"))
    )
    (net (code "42") (name "BIOP2") (class "Default")
      (node (ref "C20") (pin "M2") (pinfunction "P$2_M2") (pintype "bidirectional"))
      (node (ref "D20") (pin "M2") (pinfunction "P$2_M2") (pintype "bidirectional"))
    )
    (net (code "43") (name "BIOP4") (class "Default")
      (node (ref "C20") (pin "P2") (pinfunction "P$2_P2") (pintype "bidirectional"))
      (node (ref "D20") (pin "P2") (pinfunction "P$2_P2") (pintype "bidirectional"))
    )
    (net (code "44") (name "BIOP_1") (class "Default")
      (node (ref "AB18") (pin "AP2") (pinfunction "AP2_AP2") (pintype "input"))
    )
    (net (code "45") (name "BIOP_2") (class "Default")
      (node (ref "AB18") (pin "AR2") (pinfunction "AR2_AR2") (pintype "input"))
    )
    (net (code "46") (name "BIOP_4") (class "Default")
      (node (ref "AB19") (pin "AP2") (pinfunction "AP2_AP2") (pintype "input"))
    )
    (net (code "47") (name "BMB_00") (class "Default")
      (node (ref "AB17") (pin "AN1") (pinfunction "AN1_AN1") (pintype "input"))
      (node (ref "C19") (pin "B1") (pinfunction "P$2_B1") (pintype "bidirectional"))
      (node (ref "D19") (pin "B1") (pinfunction "P$2_B1") (pintype "bidirectional"))
    )
    (net (code "48") (name "BMB_01") (class "Default")
      (node (ref "AB17") (pin "AP1") (pinfunction "AP1_AP1") (pintype "input"))
      (node (ref "C19") (pin "D1") (pinfunction "P$2_D1") (pintype "bidirectional"))
      (node (ref "D19") (pin "D1") (pinfunction "P$2_D1") (pintype "bidirectional"))
    )
    (net (code "49") (name "BMB_02") (class "Default")
      (node (ref "AB17") (pin "AR1") (pinfunction "AR1_AR1") (pintype "input"))
      (node (ref "C19") (pin "E1") (pinfunction "P$2_E1") (pintype "bidirectional"))
      (node (ref "D19") (pin "E1") (pinfunction "P$2_E1") (pintype "bidirectional"))
    )
    (net (code "50") (name "BMB_03") (class "Default")
      (node (ref "AB18") (pin "AN1") (pinfunction "AN1_AN1") (pintype "input"))
      (node (ref "C19") (pin "J1") (pinfunction "P$2_J1") (pintype "bidirectional"))
      (node (ref "D19") (pin "J1") (pinfunction "P$2_J1") (pintype "bidirectional"))
    )
    (net (code "51") (name "BMB_03_L") (class "Default")
      (node (ref "C19") (pin "H1") (pinfunction "P$2_H1") (pintype "bidirectional"))
      (node (ref "D19") (pin "H1") (pinfunction "P$2_H1") (pintype "bidirectional"))
    )
    (net (code "52") (name "BMB_04") (class "Default")
      (node (ref "AB18") (pin "AP1") (pinfunction "AP1_AP1") (pintype "input"))
      (node (ref "C19") (pin "M1") (pinfunction "P$2_M1") (pintype "bidirectional"))
      (node (ref "D19") (pin "M1") (pinfunction "P$2_M1") (pintype "bidirectional"))
    )
    (net (code "53") (name "BMB_05") (class "Default")
      (node (ref "AB18") (pin "AR1") (pinfunction "AR1_AR1") (pintype "input"))
      (node (ref "C19") (pin "S1") (pinfunction "P$2_S1") (pintype "bidirectional"))
      (node (ref "D19") (pin "S1") (pinfunction "P$2_S1") (pintype "bidirectional"))
    )
    (net (code "54") (name "BMB_05_L") (class "Default")
      (node (ref "C19") (pin "P1") (pinfunction "P$2_P1") (pintype "bidirectional"))
      (node (ref "D19") (pin "P1") (pinfunction "P$2_P1") (pintype "bidirectional"))
    )
    (net (code "55") (name "BMB_06") (class "Default")
      (node (ref "AB19") (pin "AN1") (pinfunction "AN1_AN1") (pintype "input"))
      (node (ref "C19") (pin "E2") (pinfunction "P$2_E2") (pintype "bidirectional"))
      (node (ref "D19") (pin "E2") (pinfunction "P$2_E2") (pintype "bidirectional"))
    )
    (net (code "56") (name "BMB_06_L") (class "Default")
      (node (ref "C19") (pin "D2") (pinfunction "P$2_D2") (pintype "bidirectional"))
      (node (ref "D19") (pin "D2") (pinfunction "P$2_D2") (pintype "bidirectional"))
    )
    (net (code "57") (name "BMB_07") (class "Default")
      (node (ref "AB19") (pin "AP1") (pinfunction "AP1_AP1") (pintype "input"))
      (node (ref "C19") (pin "K2") (pinfunction "P$2_K2") (pintype "bidirectional"))
      (node (ref "D19") (pin "K2") (pinfunction "P$2_K2") (pintype "bidirectional"))
    )
    (net (code "58") (name "BMB_07_L") (class "Default")
      (node (ref "C19") (pin "H2") (pinfunction "P$2_H2") (pintype "bidirectional"))
      (node (ref "D19") (pin "H2") (pinfunction "P$2_H2") (pintype "bidirectional"))
    )
    (net (code "59") (name "BMB_08") (class "Default")
      (node (ref "AB19") (pin "AR1") (pinfunction "AR1_AR1") (pintype "input"))
      (node (ref "C19") (pin "P2") (pinfunction "P$2_P2") (pintype "bidirectional"))
      (node (ref "D19") (pin "P2") (pinfunction "P$2_P2") (pintype "bidirectional"))
    )
    (net (code "60") (name "BMB_08_L") (class "Default")
      (node (ref "C19") (pin "M2") (pinfunction "P$2_M2") (pintype "bidirectional"))
      (node (ref "D19") (pin "M2") (pinfunction "P$2_M2") (pintype "bidirectional"))
    )
    (net (code "61") (name "BMB_09") (class "Default")
      (node (ref "AB20") (pin "AN1") (pinfunction "AN1_AN1") (pintype "input"))
      (node (ref "C19") (pin "S2") (pinfunction "P$2_S2") (pintype "bidirectional"))
      (node (ref "D19") (pin "S2") (pinfunction "P$2_S2") (pintype "bidirectional"))
    )
    (net (code "62") (name "BMB_10") (class "Default")
      (node (ref "AB20") (pin "AP1") (pinfunction "AP1_AP1") (pintype "input"))
      (node (ref "C19") (pin "T2") (pinfunction "P$2_T2") (pintype "bidirectional"))
      (node (ref "D19") (pin "T2") (pinfunction "P$2_T2") (pintype "bidirectional"))
    )
    (net (code "63") (name "BMB_11") (class "Default")
      (node (ref "AB20") (pin "AR1") (pinfunction "AR1_AR1") (pintype "input"))
      (node (ref "C19") (pin "V2") (pinfunction "P$2_V2") (pintype "bidirectional"))
      (node (ref "D19") (pin "V2") (pinfunction "P$2_V2") (pintype "bidirectional"))
    )
    (net (code "64") (name "BREAK") (class "Default")
      (node (ref "A07") (pin "L2") (pinfunction "P$2_L2") (pintype "bidirectional"))
    )
    (net (code "65") (name "BREAK_CYCLE") (class "Default")
      (node (ref "A07") (pin "R2") (pinfunction "P$2_R2") (pintype "bidirectional"))
    )
    (net (code "66") (name "BREAK_L") (class "Default")
      (node (ref "A07") (pin "M2") (pinfunction "P$2_M2") (pintype "bidirectional"))
    )
    (net (code "67") (name "BRK_IN_PROG_L") (class "Default")
      (node (ref "B07") (pin "E2") (pinfunction "P$2_E2") (pintype "bidirectional"))
    )
    (net (code "68") (name "BTP1") (class "Default")
      (node (ref "C07") (pin "D2") (pinfunction "P$2_D2") (pintype "bidirectional"))
    )
    (net (code "69") (name "BTP2") (class "Default")
      (node (ref "C07") (pin "E2") (pinfunction "P$2_E2") (pintype "bidirectional"))
    )
    (net (code "70") (name "BTP3") (class "Default")
      (node (ref "C07") (pin "H2") (pinfunction "P$2_H2") (pintype "bidirectional"))
    )
    (net (code "71") (name "BTP4") (class "Default")
      (node (ref "C07") (pin "J2") (pinfunction "P$2_J2") (pintype "bidirectional"))
    )
    (net (code "72") (name "BTS_1") (class "Default")
      (node (ref "AB17") (pin "AP2") (pinfunction "AP2_AP2") (pintype "input"))
      (node (ref "C20") (pin "T2") (pinfunction "P$2_T2") (pintype "bidirectional"))
      (node (ref "D20") (pin "T2") (pinfunction "P$2_T2") (pintype "bidirectional"))
    )
    (net (code "73") (name "BTS_3") (class "Default")
      (node (ref "AB17") (pin "AR2") (pinfunction "AR2_AR2") (pintype "input"))
      (node (ref "C20") (pin "S2") (pinfunction "P$2_S2") (pintype "bidirectional"))
      (node (ref "D20") (pin "S2") (pinfunction "P$2_S2") (pintype "bidirectional"))
    )
    (net (code "74") (name "B_C1") (class "Default")
      (node (ref "AB17") (pin "BE2") (pinfunction "BE2_BE2") (pintype "input"))
      (node (ref "AB18") (pin "BE2") (pinfunction "BE2_BE2") (pintype "input"))
      (node (ref "AB19") (pin "BE2") (pinfunction "BE2_BE2") (pintype "input"))
      (node (ref "AB20") (pin "BE2") (pinfunction "BE2_BE2") (pintype "input"))
    )
    (net (code "75") (name "B_INITIALIZE") (class "Default")
      (node (ref "AB19") (pin "AR2") (pinfunction "AR2_AR2") (pintype "input"))
      (node (ref "C20") (pin "V2") (pinfunction "P$2_V2") (pintype "bidirectional"))
      (node (ref "D20") (pin "V2") (pinfunction "P$2_V2") (pintype "bidirectional"))
    )
    (net (code "76") (name "B_INT_STROBE") (class "Default")
      (node (ref "B07") (pin "D2") (pinfunction "P$2_D2") (pintype "bidirectional"))
    )
    (net (code "77") (name "B_RUN_L") (class "Default")
      (node (ref "AB17") (pin "AL2") (pinfunction "AL2_AL2") (pintype "input"))
      (node (ref "B07") (pin "U2") (pinfunction "P$2_U2") (pintype "bidirectional"))
      (node (ref "C18") (pin "S2") (pinfunction "P$2_S2") (pintype "bidirectional"))
      (node (ref "D18") (pin "S2") (pinfunction "P$2_S2") (pintype "bidirectional"))
    )
    (net (code "78") (name "B_TIME_1_L") (class "Default")
      (node (ref "C07") (pin "K2") (pinfunction "P$2_K2") (pintype "bidirectional"))
    )
    (net (code "79") (name "B_TIME_2_L") (class "Default")
      (node (ref "C07") (pin "L2") (pinfunction "P$2_L2") (pintype "bidirectional"))
    )
    (net (code "80") (name "B_TIME_3_L") (class "Default")
      (node (ref "C07") (pin "M2") (pinfunction "P$2_M2") (pintype "bidirectional"))
    )
    (net (code "81") (name "B_TIME_4_L") (class "Default")
      (node (ref "C07") (pin "P2") (pinfunction "P$2_P2") (pintype "bidirectional"))
    )
    (net (code "82") (name "B_TT_INST") (class "Default")
      (node (ref "C18") (pin "T2") (pinfunction "P$2_T2") (pintype "bidirectional"))
      (node (ref "D18") (pin "T2") (pinfunction "P$2_T2") (pintype "bidirectional"))
    )
    (net (code "83") (name "C0_L") (class "Default")
      (node (ref "C07") (pin "E1") (pinfunction "P$2_E1") (pintype "bidirectional"))
    )
    (net (code "84") (name "C1_1_CYCLE") (class "Default")
      (node (ref "AB20") (pin "AA1") (pinfunction "AA1_AA1") (pintype "open_collector"))
      (node (ref "C16") (pin "K2") (pinfunction "P$2_K2") (pintype "bidirectional"))
      (node (ref "D16") (pin "K2") (pinfunction "P$2_K2") (pintype "bidirectional"))
    )
    (net (code "85") (name "C1_ADD_ACC") (class "Default")
      (node (ref "AB19") (pin "BC1") (pinfunction "BC1_BC1") (pintype "output"))
    )
    (net (code "86") (name "C1_ADD_ACC_L") (class "Default")
      (node (ref "AB19") (pin "BV2") (pinfunction "BV2_BV2") (pintype "open_collector"))
    )
    (net (code "87") (name "C1_BADD_ACC_0_L") (class "Default")
      (node (ref "C17") (pin "S2") (pinfunction "P$2_S2") (pintype "bidirectional"))
      (node (ref "D17") (pin "S2") (pinfunction "P$2_S2") (pintype "bidirectional"))
    )
    (net (code "88") (name "C1_BREAK") (class "Default")
      (node (ref "AB19") (pin "BP1") (pinfunction "OUT_BP1") (pintype "output"))
    )
    (net (code "89") (name "C1_BREAK_CYCLE") (class "Default")
      (node (ref "AB18") (pin "BV2") (pinfunction "BV2_BV2") (pintype "open_collector"))
    )
    (net (code "90") (name "C1_BREAK_L") (class "Default")
      (node (ref "AB20") (pin "BP1") (pinfunction "OUT_BP1") (pintype "output"))
    )
    (net (code "91") (name "C1_BRK_H") (class "Default")
      (node (ref "AB20") (pin "BR1") (pinfunction "IN1_BR1") (pintype "input"))
      (node (ref "AB20") (pin "BS1") (pinfunction "IN2_BS1") (pintype "input"))
    )
    (net (code "92") (name "C1_BRK_IN_PROG") (class "Default")
      (node (ref "AB19") (pin "BU2") (pinfunction "BU2_BU2") (pintype "output"))
    )
    (net (code "93") (name "C1_BRK_IN_PROG_L") (class "Default")
      (node (ref "AB19") (pin "BU1") (pinfunction "BU1_BU1") (pintype "input"))
    )
    (net (code "94") (name "C1_BRK_L") (class "Default")
      (node (ref "AB17") (pin "BD2") (pinfunction "BD2_BD2") (pintype "input"))
      (node (ref "AB18") (pin "AU1") (pinfunction "AU1_AU1") (pintype "output"))
      (node (ref "AB18") (pin "BD1") (pinfunction "BD1_BD1") (pintype "input"))
      (node (ref "AB18") (pin "BD2") (pinfunction "BD2_BD2") (pintype "input"))
      (node (ref "AB19") (pin "BD2") (pinfunction "BD2_BD2") (pintype "input"))
      (node (ref "AB19") (pin "BR1") (pinfunction "IN1_BR1") (pintype "input"))
      (node (ref "AB19") (pin "BS1") (pinfunction "IN2_BS1") (pintype "input"))
      (node (ref "AB20") (pin "BD2") (pinfunction "BD2_BD2") (pintype "input"))
    )
    (net (code "95") (name "C1_BRK_RQST_L") (class "Default")
      (node (ref "AB19") (pin "AB1") (pinfunction "AB1_AB1") (pintype "open_collector"))
      (node (ref "C17") (pin "K2") (pinfunction "P$2_K2") (pintype "bidirectional"))
      (node (ref "D17") (pin "K2") (pinfunction "P$2_K2") (pintype "bidirectional"))
    )
    (net (code "96") (name "C1_BTS_1") (class "Default")
      (node (ref "AB17") (pin "AT2") (pinfunction "AT2_AT2") (pintype "output"))
    )
    (net (code "97") (name "C1_BTS_3") (class "Default")
      (node (ref "AB17") (pin "AS2") (pinfunction "AS2_AS2") (pintype "output"))
    )
    (net (code "98") (name "C1_B_ADD_ACC_L") (class "Default")
      (node (ref "AB19") (pin "AL2") (pinfunction "AL2_AL2") (pintype "input"))
    )
    (net (code "99") (name "C1_B_BREAK_L") (class "Default")
      (node (ref "AB18") (pin "AL2") (pinfunction "AL2_AL2") (pintype "input"))
      (node (ref "C17") (pin "P2") (pinfunction "P$2_P2") (pintype "bidirectional"))
      (node (ref "D17") (pin "P2") (pinfunction "P$2_P2") (pintype "bidirectional"))
    )
    (net (code "100") (name "C1_B_DATA_00") (class "Default")
      (node (ref "C16") (pin "B1") (pinfunction "P$2_B1") (pintype "bidirectional"))
      (node (ref "D16") (pin "B1") (pinfunction "P$2_B1") (pintype "bidirectional"))
    )
    (net (code "101") (name "C1_B_DATA_01") (class "Default")
      (node (ref "C16") (pin "D1") (pinfunction "P$2_D1") (pintype "bidirectional"))
      (node (ref "D16") (pin "D1") (pinfunction "P$2_D1") (pintype "bidirectional"))
    )
    (net (code "102") (name "C1_B_DATA_01_L") (class "Default")
      (node (ref "AB17") (pin "AJ2") (pinfunction "AJ2_AJ2") (pintype "open_collector"))
    )
    (net (code "103") (name "C1_B_DATA_02") (class "Default")
      (node (ref "C16") (pin "E1") (pinfunction "P$2_E1") (pintype "bidirectional"))
      (node (ref "D16") (pin "E1") (pinfunction "P$2_E1") (pintype "bidirectional"))
    )
    (net (code "104") (name "C1_B_DATA_02_L") (class "Default")
      (node (ref "AB17") (pin "AH2") (pinfunction "AH2_AH2") (pintype "open_collector"))
    )
    (net (code "105") (name "C1_B_DATA_002_L") (class "Default")
      (node (ref "AB17") (pin "AF2") (pinfunction "AF2_AF2") (pintype "open_collector"))
    )
    (net (code "106") (name "C1_B_DATA_03") (class "Default")
      (node (ref "C16") (pin "H1") (pinfunction "P$2_H1") (pintype "bidirectional"))
      (node (ref "D16") (pin "H1") (pinfunction "P$2_H1") (pintype "bidirectional"))
    )
    (net (code "107") (name "C1_B_DATA_03_L") (class "Default")
      (node (ref "AB18") (pin "AF2") (pinfunction "AF2_AF2") (pintype "open_collector"))
    )
    (net (code "108") (name "C1_B_DATA_04") (class "Default")
      (node (ref "C16") (pin "J1") (pinfunction "P$2_J1") (pintype "bidirectional"))
      (node (ref "D16") (pin "J1") (pinfunction "P$2_J1") (pintype "bidirectional"))
    )
    (net (code "109") (name "C1_B_DATA_04_L") (class "Default")
      (node (ref "AB18") (pin "AJ2") (pinfunction "AJ2_AJ2") (pintype "open_collector"))
    )
    (net (code "110") (name "C1_B_DATA_05") (class "Default")
      (node (ref "C16") (pin "L1") (pinfunction "P$2_L1") (pintype "bidirectional"))
      (node (ref "D16") (pin "L1") (pinfunction "P$2_L1") (pintype "bidirectional"))
    )
    (net (code "111") (name "C1_B_DATA_05_L") (class "Default")
      (node (ref "AB18") (pin "AH2") (pinfunction "AH2_AH2") (pintype "open_collector"))
    )
    (net (code "112") (name "C1_B_DATA_06") (class "Default")
      (node (ref "C16") (pin "M1") (pinfunction "P$2_M1") (pintype "bidirectional"))
      (node (ref "D16") (pin "M1") (pinfunction "P$2_M1") (pintype "bidirectional"))
    )
    (net (code "113") (name "C1_B_DATA_06_L") (class "Default")
      (node (ref "AB19") (pin "AF2") (pinfunction "AF2_AF2") (pintype "open_collector"))
    )
    (net (code "114") (name "C1_B_DATA_07") (class "Default")
      (node (ref "C16") (pin "P1") (pinfunction "P$2_P1") (pintype "bidirectional"))
      (node (ref "D16") (pin "P1") (pinfunction "P$2_P1") (pintype "bidirectional"))
    )
    (net (code "115") (name "C1_B_DATA_07_L") (class "Default")
      (node (ref "AB19") (pin "AJ2") (pinfunction "AJ2_AJ2") (pintype "open_collector"))
    )
    (net (code "116") (name "C1_B_DATA_08") (class "Default")
      (node (ref "C16") (pin "S1") (pinfunction "P$2_S1") (pintype "bidirectional"))
      (node (ref "D16") (pin "S1") (pinfunction "P$2_S1") (pintype "bidirectional"))
    )
    (net (code "117") (name "C1_B_DATA_08_L") (class "Default")
      (node (ref "AB19") (pin "AH2") (pinfunction "AH2_AH2") (pintype "open_collector"))
    )
    (net (code "118") (name "C1_B_DATA_09") (class "Default")
      (node (ref "C16") (pin "D2") (pinfunction "P$2_D2") (pintype "bidirectional"))
      (node (ref "D16") (pin "D2") (pinfunction "P$2_D2") (pintype "bidirectional"))
    )
    (net (code "119") (name "C1_B_DATA_09_L") (class "Default")
      (node (ref "AB20") (pin "AF2") (pinfunction "AF2_AF2") (pintype "open_collector"))
    )
    (net (code "120") (name "C1_B_DATA_10") (class "Default")
      (node (ref "C16") (pin "E2") (pinfunction "P$2_E2") (pintype "bidirectional"))
      (node (ref "D16") (pin "E2") (pinfunction "P$2_E2") (pintype "bidirectional"))
    )
    (net (code "121") (name "C1_B_DATA_10_L") (class "Default")
      (node (ref "AB20") (pin "AJ2") (pinfunction "AJ2_AJ2") (pintype "open_collector"))
    )
    (net (code "122") (name "C1_B_DATA_11") (class "Default")
      (node (ref "C16") (pin "H2") (pinfunction "P$2_H2") (pintype "bidirectional"))
      (node (ref "D16") (pin "H2") (pinfunction "P$2_H2") (pintype "bidirectional"))
    )
    (net (code "123") (name "C1_B_DATA_11_L") (class "Default")
      (node (ref "AB20") (pin "AH2") (pinfunction "AH2_AH2") (pintype "open_collector"))
    )
    (net (code "124") (name "C1_B_INITIALIZE_2") (class "Default")
      (node (ref "C17") (pin "V2") (pinfunction "P$2_V2") (pintype "bidirectional"))
      (node (ref "D17") (pin "V2") (pinfunction "P$2_V2") (pintype "bidirectional"))
    )
    (net (code "125") (name "C1_B_RUN_L") (class "Default")
      (node (ref "AB17") (pin "BP1") (pinfunction "OUT_BP1") (pintype "output"))
    )
    (net (code "126") (name "C1_B_WC_OVERFLOW_L") (class "Default")
      (node (ref "C16") (pin "P2") (pinfunction "P$2_P2") (pintype "bidirectional"))
      (node (ref "D16") (pin "P2") (pinfunction "P$2_P2") (pintype "bidirectional"))
    )
    (net (code "127") (name "C1_C1") (class "Default")
      (node (ref "AB17") (pin "BF1") (pinfunction "OUT_BF1") (pintype "output"))
    )
    (net (code "128") (name "C1_C1_L") (class "Default")
      (node (ref "AB17") (pin "BH1") (pinfunction "IN1_BH1") (pintype "input"))
      (node (ref "AB17") (pin "BJ1") (pinfunction "IN2_BJ1") (pintype "input"))
    )
    (net (code "129") (name "C1_CA_INCREMENT_L") (class "Default")
      (node (ref "C16") (pin "M2") (pinfunction "P$2_M2") (pintype "bidirectional"))
      (node (ref "D16") (pin "M2") (pinfunction "P$2_M2") (pintype "bidirectional"))
    )
    (net (code "130") (name "C1_CLR_AC") (class "Default")
      (node (ref "AB17") (pin "BV1") (pinfunction "BV1_BV1") (pintype "input"))
    )
    (net (code "131") (name "C1_DATA_00_L") (class "Default")
      (node (ref "AB17") (pin "BK2") (pinfunction "BK2_BK2") (pintype "open_collector"))
    )
    (net (code "132") (name "C1_DATA_01_L") (class "Default")
      (node (ref "AB17") (pin "BL2") (pinfunction "BL2_BL2") (pintype "open_collector"))
    )
    (net (code "133") (name "C1_DATA_02_L") (class "Default")
      (node (ref "AB17") (pin "BM2") (pinfunction "BM2_BM2") (pintype "open_collector"))
    )
    (net (code "134") (name "C1_DATA_03_L") (class "Default")
      (node (ref "AB18") (pin "BK2") (pinfunction "BK2_BK2") (pintype "open_collector"))
    )
    (net (code "135") (name "C1_DATA_04_L") (class "Default")
      (node (ref "AB18") (pin "BL2") (pinfunction "BL2_BL2") (pintype "open_collector"))
    )
    (net (code "136") (name "C1_DATA_05_L") (class "Default")
      (node (ref "AB18") (pin "BM2") (pinfunction "BM2_BM2") (pintype "open_collector"))
    )
    (net (code "137") (name "C1_DATA_06_L") (class "Default")
      (node (ref "AB19") (pin "BK2") (pinfunction "BK2_BK2") (pintype "open_collector"))
    )
    (net (code "138") (name "C1_DATA_07_L") (class "Default")
      (node (ref "AB19") (pin "BL2") (pinfunction "BL2_BL2") (pintype "open_collector"))
    )
    (net (code "139") (name "C1_DATA_08_L") (class "Default")
      (node (ref "AB19") (pin "BM2") (pinfunction "BM2_BM2") (pintype "open_collector"))
    )
    (net (code "140") (name "C1_DATA_09_L") (class "Default")
      (node (ref "AB20") (pin "BK2") (pinfunction "BK2_BK2") (pintype "open_collector"))
    )
    (net (code "141") (name "C1_DATA_10_L") (class "Default")
      (node (ref "AB20") (pin "BL2") (pinfunction "BL2_BL2") (pintype "open_collector"))
    )
    (net (code "142") (name "C1_DATA_11_L") (class "Default")
      (node (ref "AB20") (pin "BM2") (pinfunction "BM2_BM2") (pintype "open_collector"))
    )
    (net (code "143") (name "C1_DATA_ADD_00_L") (class "Default")
      (node (ref "AB18") (pin "AD1") (pinfunction "AD1_AD1") (pintype "open_collector"))
      (node (ref "C17") (pin "B1") (pinfunction "P$2_B1") (pintype "bidirectional"))
      (node (ref "D17") (pin "B1") (pinfunction "P$2_B1") (pintype "bidirectional"))
    )
    (net (code "144") (name "C1_DATA_ADD_01_L") (class "Default")
      (node (ref "AB18") (pin "AE1") (pinfunction "AE1_AE1") (pintype "open_collector"))
      (node (ref "C17") (pin "D1") (pinfunction "P$2_D1") (pintype "bidirectional"))
      (node (ref "D17") (pin "D1") (pinfunction "P$2_D1") (pintype "bidirectional"))
    )
    (net (code "145") (name "C1_DATA_ADD_02_L") (class "Default")
      (node (ref "AB18") (pin "AD2") (pinfunction "AD2_AD2") (pintype "open_collector"))
      (node (ref "C17") (pin "E1") (pinfunction "P$2_E1") (pintype "bidirectional"))
      (node (ref "D17") (pin "E1") (pinfunction "P$2_E1") (pintype "bidirectional"))
    )
    (net (code "146") (name "C1_DATA_ADD_03_L") (class "Default")
      (node (ref "AB18") (pin "AE2") (pinfunction "AE2_AE2") (pintype "open_collector"))
      (node (ref "C17") (pin "H1") (pinfunction "P$2_H1") (pintype "bidirectional"))
      (node (ref "D17") (pin "H1") (pinfunction "P$2_H1") (pintype "bidirectional"))
    )
    (net (code "147") (name "C1_DATA_ADD_04_L") (class "Default")
      (node (ref "AB20") (pin "AD1") (pinfunction "AD1_AD1") (pintype "open_collector"))
      (node (ref "C17") (pin "J1") (pinfunction "P$2_J1") (pintype "bidirectional"))
      (node (ref "D17") (pin "J1") (pinfunction "P$2_J1") (pintype "bidirectional"))
    )
    (net (code "148") (name "C1_DATA_ADD_05_L") (class "Default")
      (node (ref "AB20") (pin "AE1") (pinfunction "AE1_AE1") (pintype "open_collector"))
      (node (ref "C17") (pin "L1") (pinfunction "P$2_L1") (pintype "bidirectional"))
      (node (ref "D17") (pin "L1") (pinfunction "P$2_L1") (pintype "bidirectional"))
    )
    (net (code "149") (name "C1_DATA_ADD_06_L") (class "Default")
      (node (ref "AB20") (pin "AD2") (pinfunction "AD2_AD2") (pintype "open_collector"))
      (node (ref "C17") (pin "M1") (pinfunction "P$2_M1") (pintype "bidirectional"))
      (node (ref "D17") (pin "M1") (pinfunction "P$2_M1") (pintype "bidirectional"))
    )
    (net (code "150") (name "C1_DATA_ADD_07_L") (class "Default")
      (node (ref "AB20") (pin "AE2") (pinfunction "AE2_AE2") (pintype "open_collector"))
      (node (ref "C17") (pin "P1") (pinfunction "P$2_P1") (pintype "bidirectional"))
      (node (ref "D17") (pin "P1") (pinfunction "P$2_P1") (pintype "bidirectional"))
    )
    (net (code "151") (name "C1_DATA_ADD_08_L") (class "Default")
      (node (ref "AB19") (pin "AD1") (pinfunction "AD1_AD1") (pintype "open_collector"))
      (node (ref "C17") (pin "S1") (pinfunction "P$2_S1") (pintype "bidirectional"))
      (node (ref "D17") (pin "S1") (pinfunction "P$2_S1") (pintype "bidirectional"))
    )
    (net (code "152") (name "C1_DATA_ADD_09_L") (class "Default")
      (node (ref "AB19") (pin "AE1") (pinfunction "AE1_AE1") (pintype "open_collector"))
      (node (ref "C17") (pin "D2") (pinfunction "P$2_D2") (pintype "bidirectional"))
      (node (ref "D17") (pin "D2") (pinfunction "P$2_D2") (pintype "bidirectional"))
    )
    (net (code "153") (name "C1_DATA_ADD_10_L") (class "Default")
      (node (ref "AB19") (pin "AD2") (pinfunction "AD2_AD2") (pintype "open_collector"))
      (node (ref "C17") (pin "E2") (pinfunction "P$2_E2") (pintype "bidirectional"))
      (node (ref "D17") (pin "E2") (pinfunction "P$2_E2") (pintype "bidirectional"))
    )
    (net (code "154") (name "C1_DATA_ADD_11_L") (class "Default")
      (node (ref "AB19") (pin "AE2") (pinfunction "AE2_AE2") (pintype "open_collector"))
      (node (ref "C17") (pin "H2") (pinfunction "P$2_H2") (pintype "bidirectional"))
      (node (ref "D17") (pin "H2") (pinfunction "P$2_H2") (pintype "bidirectional"))
    )
    (net (code "155") (name "C1_DATA_IN") (class "Default")
      (node (ref "AB20") (pin "AB1") (pinfunction "AB1_AB1") (pintype "open_collector"))
      (node (ref "C17") (pin "M2") (pinfunction "P$2_M2") (pintype "bidirectional"))
      (node (ref "D17") (pin "M2") (pinfunction "P$2_M2") (pintype "bidirectional"))
    )
    (net (code "156") (name "C1_EMA_0_L") (class "Default")
      (node (ref "AB17") (pin "BP2") (pinfunction "BP2_BP2") (pintype "input"))
    )
    (net (code "157") (name "C1_EMA_1_L") (class "Default")
      (node (ref "AB17") (pin "BR2") (pinfunction "BR2_BR2") (pintype "input"))
    )
    (net (code "158") (name "C1_EMA_2_L") (class "Default")
      (node (ref "AB17") (pin "BS2") (pinfunction "BS2_BS2") (pintype "input"))
    )
    (net (code "159") (name "C1_EXT_DATA_ADD_0_L") (class "Default")
      (node (ref "AB17") (pin "AE1") (pinfunction "AE1_AE1") (pintype "open_collector"))
      (node (ref "C16") (pin "V2") (pinfunction "P$2_V2") (pintype "bidirectional"))
      (node (ref "D16") (pin "V2") (pinfunction "P$2_V2") (pintype "bidirectional"))
    )
    (net (code "160") (name "C1_EXT_DATA_ADD_1_L") (class "Default")
      (node (ref "AB17") (pin "AD2") (pinfunction "AD2_AD2") (pintype "open_collector"))
      (node (ref "C16") (pin "T2") (pinfunction "P$2_T2") (pintype "bidirectional"))
      (node (ref "D16") (pin "T2") (pinfunction "P$2_T2") (pintype "bidirectional"))
    )
    (net (code "161") (name "C1_EXT_DATA_ADD_2_L") (class "Default")
      (node (ref "AB17") (pin "AE2") (pinfunction "AE2_AE2") (pintype "open_collector"))
      (node (ref "C16") (pin "S2") (pinfunction "P$2_S2") (pintype "bidirectional"))
      (node (ref "D16") (pin "S2") (pinfunction "P$2_S2") (pintype "bidirectional"))
    )
    (net (code "162") (name "C1_INITIALIZE_L") (class "Default")
      (node (ref "AB19") (pin "BA1") (pinfunction "BA1_BA1") (pintype "open_collector"))
    )
    (net (code "163") (name "C1_INT_RQST_L") (class "Default")
      (node (ref "AB18") (pin "BU1") (pinfunction "BU1_BU1") (pintype "input"))
    )
    (net (code "164") (name "C1_IOP_1") (class "Default")
      (node (ref "AB18") (pin "AT2") (pinfunction "AT2_AT2") (pintype "output"))
    )
    (net (code "165") (name "C1_IOP_2") (class "Default")
      (node (ref "AB18") (pin "AS2") (pinfunction "AS2_AS2") (pintype "output"))
    )
    (net (code "166") (name "C1_IOP_4") (class "Default")
      (node (ref "AB19") (pin "AT2") (pinfunction "AT2_AT2") (pintype "output"))
    )
    (net (code "167") (name "C1_IO_PAUSE") (class "Default")
      (node (ref "AB18") (pin "BR1") (pinfunction "IN1_BR1") (pintype "input"))
      (node (ref "AB18") (pin "BS1") (pinfunction "IN2_BS1") (pintype "input"))
    )
    (net (code "168") (name "C1_IO_PAUSE_L") (class "Default")
      (node (ref "AB18") (pin "BP1") (pinfunction "OUT_BP1") (pintype "output"))
    )
    (net (code "169") (name "C1_L") (class "Default")
      (node (ref "C07") (pin "H1") (pinfunction "P$2_H1") (pintype "bidirectional"))
    )
    (net (code "170") (name "C1_MA_00_L") (class "Default")
      (node (ref "AB18") (pin "BN2") (pinfunction "BN2_BN2") (pintype "input"))
    )
    (net (code "171") (name "C1_MA_01_L") (class "Default")
      (node (ref "AB18") (pin "BP2") (pinfunction "BP2_BP2") (pintype "input"))
    )
    (net (code "172") (name "C1_MA_02_L") (class "Default")
      (node (ref "AB18") (pin "BR2") (pinfunction "BR2_BR2") (pintype "input"))
    )
    (net (code "173") (name "C1_MA_03_L") (class "Default")
      (node (ref "AB18") (pin "BS2") (pinfunction "BS2_BS2") (pintype "input"))
    )
    (net (code "174") (name "C1_MA_04_L") (class "Default")
      (node (ref "AB20") (pin "BN2") (pinfunction "BN2_BN2") (pintype "input"))
    )
    (net (code "175") (name "C1_MA_05_L") (class "Default")
      (node (ref "AB20") (pin "BP2") (pinfunction "BP2_BP2") (pintype "input"))
    )
    (net (code "176") (name "C1_MA_06_L") (class "Default")
      (node (ref "AB20") (pin "BR2") (pinfunction "BR2_BR2") (pintype "input"))
    )
    (net (code "177") (name "C1_MA_07_L") (class "Default")
      (node (ref "AB20") (pin "BS2") (pinfunction "BS2_BS2") (pintype "input"))
    )
    (net (code "178") (name "C1_MA_08_L") (class "Default")
      (node (ref "AB19") (pin "BN2") (pinfunction "BN2_BN2") (pintype "input"))
    )
    (net (code "179") (name "C1_MA_09_L") (class "Default")
      (node (ref "AB19") (pin "BP2") (pinfunction "BP2_BP2") (pintype "input"))
    )
    (net (code "180") (name "C1_MA_10_L") (class "Default")
      (node (ref "AB19") (pin "BR2") (pinfunction "BR2_BR2") (pintype "input"))
    )
    (net (code "181") (name "C1_MA_11_L") (class "Default")
      (node (ref "AB19") (pin "BS2") (pinfunction "BS2_BS2") (pintype "input"))
    )
    (net (code "182") (name "C1_MB_INCREMENT_L") (class "Default")
      (node (ref "C17") (pin "T2") (pinfunction "P$2_T2") (pintype "bidirectional"))
      (node (ref "D17") (pin "T2") (pinfunction "P$2_T2") (pintype "bidirectional"))
    )
    (net (code "183") (name "C1_MD_00_L") (class "Default")
      (node (ref "AB17") (pin "BF2") (pinfunction "BF2_BF2") (pintype "open_collector"))
    )
    (net (code "184") (name "C1_MD_01_L") (class "Default")
      (node (ref "AB17") (pin "BH2") (pinfunction "BH2_BH2") (pintype "open_collector"))
    )
    (net (code "185") (name "C1_MD_02_L") (class "Default")
      (node (ref "AB17") (pin "BJ2") (pinfunction "BJ2_BJ2") (pintype "open_collector"))
    )
    (net (code "186") (name "C1_MD_03_L") (class "Default")
      (node (ref "AB18") (pin "BF2") (pinfunction "BF2_BF2") (pintype "open_collector"))
    )
    (net (code "187") (name "C1_MD_04_L") (class "Default")
      (node (ref "AB18") (pin "BH2") (pinfunction "BH2_BH2") (pintype "open_collector"))
    )
    (net (code "188") (name "C1_MD_05_L") (class "Default")
      (node (ref "AB18") (pin "BJ2") (pinfunction "BJ2_BJ2") (pintype "open_collector"))
    )
    (net (code "189") (name "C1_MD_06_L") (class "Default")
      (node (ref "AB19") (pin "BF2") (pinfunction "BF2_BF2") (pintype "open_collector"))
    )
    (net (code "190") (name "C1_MD_07_L") (class "Default")
      (node (ref "AB19") (pin "BH2") (pinfunction "BH2_BH2") (pintype "open_collector"))
    )
    (net (code "191") (name "C1_MD_08_L") (class "Default")
      (node (ref "AB19") (pin "BJ2") (pinfunction "BJ2_BJ2") (pintype "open_collector"))
    )
    (net (code "192") (name "C1_MD_09_L") (class "Default")
      (node (ref "AB20") (pin "BF2") (pinfunction "BF2_BF2") (pintype "open_collector"))
    )
    (net (code "193") (name "C1_MD_10_L") (class "Default")
      (node (ref "AB20") (pin "BH2") (pinfunction "BH2_BH2") (pintype "open_collector"))
    )
    (net (code "194") (name "C1_MD_11_L") (class "Default")
      (node (ref "AB20") (pin "BJ2") (pinfunction "BJ2_BJ2") (pintype "open_collector"))
    )
    (net (code "195") (name "C1_MD_DIR") (class "Default")
      (node (ref "AB20") (pin "BU1") (pinfunction "BU1_BU1") (pintype "input"))
    )
    (net (code "196") (name "C1_SKIP_L") (class "Default")
      (node (ref "AB17") (pin "BU1") (pinfunction "BU1_BU1") (pintype "input"))
    )
    (net (code "197") (name "DATA_00_L") (class "Default")
      (node (ref "A07") (pin "R1") (pinfunction "P$2_R1") (pintype "bidirectional"))
    )
    (net (code "198") (name "DATA_01_L") (class "Default")
      (node (ref "A07") (pin "S1") (pinfunction "P$2_S1") (pintype "bidirectional"))
    )
    (net (code "199") (name "DATA_02_L") (class "Default")
      (node (ref "A07") (pin "U1") (pinfunction "P$2_U1") (pintype "bidirectional"))
    )
    (net (code "200") (name "DATA_03_L") (class "Default")
      (node (ref "A07") (pin "V1") (pinfunction "P$2_V1") (pintype "bidirectional"))
    )
    (net (code "201") (name "DATA_04_L") (class "Default")
      (node (ref "B07") (pin "R1") (pinfunction "P$2_R1") (pintype "bidirectional"))
    )
    (net (code "202") (name "DATA_05_L") (class "Default")
      (node (ref "B07") (pin "S1") (pinfunction "P$2_S1") (pintype "bidirectional"))
    )
    (net (code "203") (name "DATA_06_L") (class "Default")
      (node (ref "B07") (pin "U1") (pinfunction "P$2_U1") (pintype "bidirectional"))
    )
    (net (code "204") (name "DATA_07_L") (class "Default")
      (node (ref "B07") (pin "V1") (pinfunction "P$2_V1") (pintype "bidirectional"))
    )
    (net (code "205") (name "DATA_08_L") (class "Default")
      (node (ref "D07") (pin "R1") (pinfunction "P$2_R1") (pintype "bidirectional"))
    )
    (net (code "206") (name "DATA_09_L") (class "Default")
      (node (ref "D07") (pin "S1") (pinfunction "P$2_S1") (pintype "bidirectional"))
    )
    (net (code "207") (name "DATA_10_L") (class "Default")
      (node (ref "D07") (pin "U1") (pinfunction "P$2_U1") (pintype "bidirectional"))
    )
    (net (code "208") (name "DATA_11_L") (class "Default")
      (node (ref "D07") (pin "V1") (pinfunction "P$2_V1") (pintype "bidirectional"))
    )
    (net (code "209") (name "EMA_0_L") (class "Default")
      (node (ref "A07") (pin "D2") (pinfunction "P$2_D2") (pintype "bidirectional"))
    )
    (net (code "210") (name "EMA_1_L") (class "Default")
      (node (ref "A07") (pin "E2") (pinfunction "P$2_E2") (pintype "bidirectional"))
    )
    (net (code "211") (name "EMA_2_L") (class "Default")
      (node (ref "A07") (pin "H2") (pinfunction "P$2_H2") (pintype "bidirectional"))
    )
    (net (code "212") (name "GND") (class "Default")
      (node (ref "A07") (pin "C1") (pinfunction "P$2_C1") (pintype "bidirectional"))
      (node (ref "A07") (pin "C2") (pinfunction "P$2_C2") (pintype "bidirectional"))
      (node (ref "A07") (pin "F1") (pinfunction "P$2_F1") (pintype "bidirectional"))
      (node (ref "A07") (pin "F2") (pinfunction "P$2_F2") (pintype "bidirectional"))
      (node (ref "A07") (pin "N1") (pinfunction "P$2_N1") (pintype "bidirectional"))
      (node (ref "A07") (pin "N2") (pinfunction "P$2_N2") (pintype "bidirectional"))
      (node (ref "A07") (pin "T1") (pinfunction "P$2_T1") (pintype "bidirectional"))
      (node (ref "A07") (pin "T2") (pinfunction "P$2_T2") (pintype "bidirectional"))
      (node (ref "AB17") (pin "AK2") (pinfunction "AK2_AK2") (pintype "input"))
      (node (ref "AB17") (pin "BD1") (pinfunction "BD1_BD1") (pintype "input"))
      (node (ref "AB17") (pin "BK1") (pinfunction "IN1_BK1") (pintype "input"))
      (node (ref "AB17") (pin "BL1") (pinfunction "IN2_BL1") (pintype "input"))
      (node (ref "AB17") (pin "BN2") (pinfunction "BN2_BN2") (pintype "input"))
      (node (ref "AB18") (pin "AK2") (pinfunction "AK2_AK2") (pintype "input"))
      (node (ref "AB18") (pin "BH1") (pinfunction "IN1_BH1") (pintype "input"))
      (node (ref "AB18") (pin "BJ1") (pinfunction "IN2_BJ1") (pintype "input"))
      (node (ref "AB18") (pin "BK1") (pinfunction "IN1_BK1") (pintype "input"))
      (node (ref "AB18") (pin "BL1") (pinfunction "IN2_BL1") (pintype "input"))
      (node (ref "AB18") (pin "BV1") (pinfunction "BV1_BV1") (pintype "input"))
      (node (ref "AB19") (pin "AK2") (pinfunction "AK2_AK2") (pintype "input"))
      (node (ref "AB19") (pin "AV1") (pinfunction "AV1_AV1") (pintype "input"))
      (node (ref "AB19") (pin "BH1") (pinfunction "IN1_BH1") (pintype "input"))
      (node (ref "AB19") (pin "BJ1") (pinfunction "IN2_BJ1") (pintype "input"))
      (node (ref "AB19") (pin "BK1") (pinfunction "IN1_BK1") (pintype "input"))
      (node (ref "AB19") (pin "BL1") (pinfunction "IN2_BL1") (pintype "input"))
      (node (ref "AB19") (pin "BV1") (pinfunction "BV1_BV1") (pintype "input"))
      (node (ref "AB20") (pin "AK2") (pinfunction "AK2_AK2") (pintype "input"))
      (node (ref "AB20") (pin "AL2") (pinfunction "AL2_AL2") (pintype "input"))
      (node (ref "AB20") (pin "AP2") (pinfunction "AP2_AP2") (pintype "input"))
      (node (ref "AB20") (pin "AR2") (pinfunction "AR2_AR2") (pintype "input"))
      (node (ref "AB20") (pin "AV1") (pinfunction "AV1_AV1") (pintype "input"))
      (node (ref "AB20") (pin "BD1") (pinfunction "BD1_BD1") (pintype "input"))
      (node (ref "AB20") (pin "BH1") (pinfunction "IN1_BH1") (pintype "input"))
      (node (ref "AB20") (pin "BJ1") (pinfunction "IN2_BJ1") (pintype "input"))
      (node (ref "AB20") (pin "BK1") (pinfunction "IN1_BK1") (pintype "input"))
      (node (ref "AB20") (pin "BL1") (pinfunction "IN2_BL1") (pintype "input"))
      (node (ref "AB20") (pin "BV1") (pinfunction "BV1_BV1") (pintype "input"))
      (node (ref "B07") (pin "C1") (pinfunction "P$2_C1") (pintype "bidirectional"))
      (node (ref "B07") (pin "C2") (pinfunction "P$2_C2") (pintype "bidirectional"))
      (node (ref "B07") (pin "F1") (pinfunction "P$2_F1") (pintype "bidirectional"))
      (node (ref "B07") (pin "F2") (pinfunction "P$2_F2") (pintype "bidirectional"))
      (node (ref "B07") (pin "N1") (pinfunction "P$2_N1") (pintype "bidirectional"))
      (node (ref "B07") (pin "N2") (pinfunction "P$2_N2") (pintype "bidirectional"))
      (node (ref "B07") (pin "T1") (pinfunction "P$2_T1") (pintype "bidirectional"))
      (node (ref "B07") (pin "T2") (pinfunction "P$2_T2") (pintype "bidirectional"))
      (node (ref "C07") (pin "C1") (pinfunction "P$2_C1") (pintype "bidirectional"))
      (node (ref "C07") (pin "C2") (pinfunction "P$2_C2") (pintype "bidirectional"))
      (node (ref "C07") (pin "F1") (pinfunction "P$2_F1") (pintype "bidirectional"))
      (node (ref "C07") (pin "F2") (pinfunction "P$2_F2") (pintype "bidirectional"))
      (node (ref "C07") (pin "N1") (pinfunction "P$2_N1") (pintype "bidirectional"))
      (node (ref "C07") (pin "N2") (pinfunction "P$2_N2") (pintype "bidirectional"))
      (node (ref "C07") (pin "T1") (pinfunction "P$2_T1") (pintype "bidirectional"))
      (node (ref "C07") (pin "T2") (pinfunction "P$2_T2") (pintype "bidirectional"))
      (node (ref "D07") (pin "C1") (pinfunction "P$2_C1") (pintype "bidirectional"))
      (node (ref "D07") (pin "C2") (pinfunction "P$2_C2") (pintype "bidirectional"))
      (node (ref "D07") (pin "F1") (pinfunction "P$2_F1") (pintype "bidirectional"))
      (node (ref "D07") (pin "F2") (pinfunction "P$2_F2") (pintype "bidirectional"))
      (node (ref "D07") (pin "N1") (pinfunction "P$2_N1") (pintype "bidirectional"))
      (node (ref "D07") (pin "N2") (pinfunction "P$2_N2") (pintype "bidirectional"))
      (node (ref "D07") (pin "T1") (pinfunction "P$2_T1") (pintype "bidirectional"))
      (node (ref "D07") (pin "T2") (pinfunction "P$2_T2") (pintype "bidirectional"))
    )
    (net (code "213") (name "INITIALIZE") (class "Default")
      (node (ref "C07") (pin "R1") (pinfunction "P$2_R1") (pintype "bidirectional"))
    )
    (net (code "214") (name "INT_RQST_BUS_L") (class "Default")
      (node (ref "AB18") (pin "AB1") (pinfunction "AB1_AB1") (pintype "open_collector"))
      (node (ref "C18") (pin "M2") (pinfunction "P$2_M2") (pintype "bidirectional"))
      (node (ref "D18") (pin "M2") (pinfunction "P$2_M2") (pintype "bidirectional"))
    )
    (net (code "215") (name "INT_RQST_L") (class "Default")
      (node (ref "C07") (pin "P1") (pinfunction "P$2_P1") (pintype "bidirectional"))
    )
    (net (code "216") (name "IO_PAUSE_L") (class "Default")
      (node (ref "C07") (pin "D1") (pinfunction "P$2_D1") (pintype "bidirectional"))
    )
    (net (code "217") (name "LINE_MUX_L") (class "Default")
      (node (ref "C18") (pin "V2") (pinfunction "P$2_V2") (pintype "bidirectional"))
      (node (ref "D18") (pin "V2") (pinfunction "P$2_V2") (pintype "bidirectional"))
    )
    (net (code "218") (name "MA_00_L") (class "Default")
      (node (ref "A07") (pin "D1") (pinfunction "P$2_D1") (pintype "bidirectional"))
    )
    (net (code "219") (name "MA_01_L") (class "Default")
      (node (ref "A07") (pin "E1") (pinfunction "P$2_E1") (pintype "bidirectional"))
    )
    (net (code "220") (name "MA_02_L") (class "Default")
      (node (ref "A07") (pin "H1") (pinfunction "P$2_H1") (pintype "bidirectional"))
    )
    (net (code "221") (name "MA_03_L") (class "Default")
      (node (ref "A07") (pin "J1") (pinfunction "P$2_J1") (pintype "bidirectional"))
    )
    (net (code "222") (name "MA_04_L") (class "Default")
      (node (ref "B07") (pin "D1") (pinfunction "P$2_D1") (pintype "bidirectional"))
    )
    (net (code "223") (name "MA_05_L") (class "Default")
      (node (ref "B07") (pin "E1") (pinfunction "P$2_E1") (pintype "bidirectional"))
    )
    (net (code "224") (name "MA_06_L") (class "Default")
      (node (ref "B07") (pin "H1") (pinfunction "P$2_H1") (pintype "bidirectional"))
    )
    (net (code "225") (name "MA_07_L") (class "Default")
      (node (ref "B07") (pin "J1") (pinfunction "P$2_J1") (pintype "bidirectional"))
    )
    (net (code "226") (name "MA_08_L") (class "Default")
      (node (ref "D07") (pin "D1") (pinfunction "P$2_D1") (pintype "bidirectional"))
    )
    (net (code "227") (name "MA_09_L") (class "Default")
      (node (ref "D07") (pin "E1") (pinfunction "P$2_E1") (pintype "bidirectional"))
    )
    (net (code "228") (name "MA_10_L") (class "Default")
      (node (ref "D07") (pin "H1") (pinfunction "P$2_H1") (pintype "bidirectional"))
    )
    (net (code "229") (name "MA_11_L") (class "Default")
      (node (ref "D07") (pin "J1") (pinfunction "P$2_J1") (pintype "bidirectional"))
    )
    (net (code "230") (name "MBM_04_L") (class "Default")
      (node (ref "C19") (pin "L1") (pinfunction "P$2_L1") (pintype "bidirectional"))
      (node (ref "D19") (pin "L1") (pinfunction "P$2_L1") (pintype "bidirectional"))
    )
    (net (code "231") (name "MD_00_L") (class "Default")
      (node (ref "A07") (pin "K1") (pinfunction "P$2_K1") (pintype "bidirectional"))
    )
    (net (code "232") (name "MD_01_L") (class "Default")
      (node (ref "A07") (pin "L1") (pinfunction "P$2_L1") (pintype "bidirectional"))
    )
    (net (code "233") (name "MD_02_L") (class "Default")
      (node (ref "A07") (pin "M1") (pinfunction "P$2_M1") (pintype "bidirectional"))
    )
    (net (code "234") (name "MD_03_L") (class "Default")
      (node (ref "A07") (pin "P1") (pinfunction "P$2_P1") (pintype "bidirectional"))
    )
    (net (code "235") (name "MD_04_L") (class "Default")
      (node (ref "B07") (pin "K1") (pinfunction "P$2_K1") (pintype "bidirectional"))
    )
    (net (code "236") (name "MD_05_L") (class "Default")
      (node (ref "B07") (pin "L1") (pinfunction "P$2_L1") (pintype "bidirectional"))
    )
    (net (code "237") (name "MD_06_L") (class "Default")
      (node (ref "B07") (pin "M1") (pinfunction "P$2_M1") (pintype "bidirectional"))
    )
    (net (code "238") (name "MD_07_L") (class "Default")
      (node (ref "B07") (pin "P1") (pinfunction "P$2_P1") (pintype "bidirectional"))
    )
    (net (code "239") (name "MD_08_L") (class "Default")
      (node (ref "D07") (pin "K1") (pinfunction "P$2_K1") (pintype "bidirectional"))
    )
    (net (code "240") (name "MD_09_L") (class "Default")
      (node (ref "D07") (pin "L1") (pinfunction "P$2_L1") (pintype "bidirectional"))
    )
    (net (code "241") (name "MD_10_L") (class "Default")
      (node (ref "D07") (pin "M1") (pinfunction "P$2_M1") (pintype "bidirectional"))
    )
    (net (code "242") (name "MD_11_L") (class "Default")
      (node (ref "D07") (pin "P1") (pinfunction "P$2_P1") (pintype "bidirectional"))
    )
    (net (code "243") (name "MD_DIR") (class "Default")
      (node (ref "A07") (pin "K2") (pinfunction "P$2_K2") (pintype "bidirectional"))
    )
    (net (code "244") (name "Net-(AB17-PadAM2)") (class "Default")
      (node (ref "AB17") (pin "AM2") (pinfunction "AM2_AM2") (pintype "output"))
      (node (ref "AB17") (pin "AV1") (pinfunction "AV1_AV1") (pintype "input"))
    )
    (net (code "245") (name "Net-(AB17N-IN1)") (class "Default")
      (node (ref "AB17") (pin "AU1") (pinfunction "AU1_AU1") (pintype "output"))
      (node (ref "AB17") (pin "BR1") (pinfunction "IN1_BR1") (pintype "input"))
      (node (ref "AB17") (pin "BS1") (pinfunction "IN2_BS1") (pintype "input"))
    )
    (net (code "246") (name "Net-(AB18-PadAM2)") (class "Default")
      (node (ref "AB18") (pin "AM2") (pinfunction "AM2_AM2") (pintype "output"))
      (node (ref "AB18") (pin "AV1") (pinfunction "AV1_AV1") (pintype "input"))
    )
    (net (code "247") (name "Net-(AB19-PadAM2)") (class "Default")
      (node (ref "AB19") (pin "AM2") (pinfunction "AM2_AM2") (pintype "output"))
      (node (ref "AB19") (pin "BD1") (pinfunction "BD1_BD1") (pintype "input"))
    )
    (net (code "248") (name "POWER_OK") (class "Default")
      (node (ref "B07") (pin "V2") (pinfunction "P$2_V2") (pintype "bidirectional"))
    )
    (net (code "249") (name "SKIP_BUS_L") (class "Default")
      (node (ref "AB17") (pin "AB1") (pinfunction "AB1_AB1") (pintype "open_collector"))
      (node (ref "C18") (pin "K2") (pinfunction "P$2_K2") (pintype "bidirectional"))
      (node (ref "D18") (pin "K2") (pinfunction "P$2_K2") (pintype "bidirectional"))
    )
    (net (code "250") (name "SKIP_L") (class "Default")
      (node (ref "C07") (pin "S1") (pinfunction "P$2_S1") (pintype "bidirectional"))
    )
    (net (code "251") (name "VCC") (class "Default")
      (node (ref "A07") (pin "A2") (pinfunction "P$2_A2") (pintype "bidirectional"))
      (node (ref "B07") (pin "A2") (pinfunction "P$2_A2") (pintype "bidirectional"))
      (node (ref "C07") (pin "A2") (pinfunction "P$2_A2") (pintype "bidirectional"))
    )
    (net (code "252") (name "unconnected-(AB17-PadAD1)") (class "Default")
      (node (ref "AB17") (pin "AD1") (pinfunction "AD1_AD1") (pintype "open_collector"))
    )
    (net (code "253") (name "unconnected-(AB17-PadAN2)") (class "Default")
      (node (ref "AB17") (pin "AN2") (pinfunction "AN2_AN2") (pintype "output"))
    )
    (net (code "254") (name "unconnected-(AB17-PadBA1)") (class "Default")
      (node (ref "AB17") (pin "BA1") (pinfunction "BA1_BA1") (pintype "open_collector"))
    )
    (net (code "255") (name "unconnected-(AB17-PadBB1)") (class "Default")
      (node (ref "AB17") (pin "BB1") (pinfunction "BB1_BB1") (pintype "open_collector"))
    )
    (net (code "256") (name "unconnected-(AB17-PadBC1)") (class "Default")
      (node (ref "AB17") (pin "BC1") (pinfunction "BC1_BC1") (pintype "output"))
    )
    (net (code "257") (name "unconnected-(AB17-PadBE1)") (class "Default")
      (node (ref "AB17") (pin "BE1") (pinfunction "BE1_BE1") (pintype "output"))
    )
    (net (code "258") (name "unconnected-(AB17-PadBU2)") (class "Default")
      (node (ref "AB17") (pin "BU2") (pinfunction "BU2_BU2") (pintype "output"))
    )
    (net (code "259") (name "unconnected-(AB17-PadBV2)") (class "Default")
      (node (ref "AB17") (pin "BV2") (pinfunction "BV2_BV2") (pintype "open_collector"))
    )
    (net (code "260") (name "unconnected-(AB17O-OUT-PadBM1)") (class "Default")
      (node (ref "AB17") (pin "BM1") (pinfunction "OUT_BM1") (pintype "output"))
    )
    (net (code "261") (name "unconnected-(AB18-PadAA1)") (class "Default")
      (node (ref "AB18") (pin "AA1") (pinfunction "AA1_AA1") (pintype "open_collector"))
    )
    (net (code "262") (name "unconnected-(AB18-PadAN2)") (class "Default")
      (node (ref "AB18") (pin "AN2") (pinfunction "AN2_AN2") (pintype "output"))
    )
    (net (code "263") (name "unconnected-(AB18-PadBA1)") (class "Default")
      (node (ref "AB18") (pin "BA1") (pinfunction "BA1_BA1") (pintype "open_collector"))
    )
    (net (code "264") (name "unconnected-(AB18-PadBB1)") (class "Default")
      (node (ref "AB18") (pin "BB1") (pinfunction "BB1_BB1") (pintype "open_collector"))
    )
    (net (code "265") (name "unconnected-(AB18-PadBC1)") (class "Default")
      (node (ref "AB18") (pin "BC1") (pinfunction "BC1_BC1") (pintype "output"))
    )
    (net (code "266") (name "unconnected-(AB18-PadBE1)") (class "Default")
      (node (ref "AB18") (pin "BE1") (pinfunction "BE1_BE1") (pintype "output"))
    )
    (net (code "267") (name "unconnected-(AB18-PadBU2)") (class "Default")
      (node (ref "AB18") (pin "BU2") (pinfunction "BU2_BU2") (pintype "output"))
    )
    (net (code "268") (name "unconnected-(AB18O-OUT-PadBM1)") (class "Default")
      (node (ref "AB18") (pin "BM1") (pinfunction "OUT_BM1") (pintype "output"))
    )
    (net (code "269") (name "unconnected-(AB18P-OUT-PadBF1)") (class "Default")
      (node (ref "AB18") (pin "BF1") (pinfunction "OUT_BF1") (pintype "output"))
    )
    (net (code "270") (name "unconnected-(AB19-PadAA1)") (class "Default")
      (node (ref "AB19") (pin "AA1") (pinfunction "AA1_AA1") (pintype "open_collector"))
    )
    (net (code "271") (name "unconnected-(AB19-PadAN2)") (class "Default")
      (node (ref "AB19") (pin "AN2") (pinfunction "AN2_AN2") (pintype "output"))
    )
    (net (code "272") (name "unconnected-(AB19-PadAS2)") (class "Default")
      (node (ref "AB19") (pin "AS2") (pinfunction "AS2_AS2") (pintype "output"))
    )
    (net (code "273") (name "unconnected-(AB19-PadAU1)") (class "Default")
      (node (ref "AB19") (pin "AU1") (pinfunction "AU1_AU1") (pintype "output"))
    )
    (net (code "274") (name "unconnected-(AB19-PadBB1)") (class "Default")
      (node (ref "AB19") (pin "BB1") (pinfunction "BB1_BB1") (pintype "open_collector"))
    )
    (net (code "275") (name "unconnected-(AB19-PadBE1)") (class "Default")
      (node (ref "AB19") (pin "BE1") (pinfunction "BE1_BE1") (pintype "output"))
    )
    (net (code "276") (name "unconnected-(AB19O-OUT-PadBM1)") (class "Default")
      (node (ref "AB19") (pin "BM1") (pinfunction "OUT_BM1") (pintype "output"))
    )
    (net (code "277") (name "unconnected-(AB19P-OUT-PadBF1)") (class "Default")
      (node (ref "AB19") (pin "BF1") (pinfunction "OUT_BF1") (pintype "output"))
    )
    (net (code "278") (name "unconnected-(AB20-PadAM2)") (class "Default")
      (node (ref "AB20") (pin "AM2") (pinfunction "AM2_AM2") (pintype "output"))
    )
    (net (code "279") (name "unconnected-(AB20-PadAN2)") (class "Default")
      (node (ref "AB20") (pin "AN2") (pinfunction "AN2_AN2") (pintype "output"))
    )
    (net (code "280") (name "unconnected-(AB20-PadAS2)") (class "Default")
      (node (ref "AB20") (pin "AS2") (pinfunction "AS2_AS2") (pintype "output"))
    )
    (net (code "281") (name "unconnected-(AB20-PadAT2)") (class "Default")
      (node (ref "AB20") (pin "AT2") (pinfunction "AT2_AT2") (pintype "output"))
    )
    (net (code "282") (name "unconnected-(AB20-PadAU1)") (class "Default")
      (node (ref "AB20") (pin "AU1") (pinfunction "AU1_AU1") (pintype "output"))
    )
    (net (code "283") (name "unconnected-(AB20-PadBA1)") (class "Default")
      (node (ref "AB20") (pin "BA1") (pinfunction "BA1_BA1") (pintype "open_collector"))
    )
    (net (code "284") (name "unconnected-(AB20-PadBB1)") (class "Default")
      (node (ref "AB20") (pin "BB1") (pinfunction "BB1_BB1") (pintype "open_collector"))
    )
    (net (code "285") (name "unconnected-(AB20-PadBC1)") (class "Default")
      (node (ref "AB20") (pin "BC1") (pinfunction "BC1_BC1") (pintype "output"))
    )
    (net (code "286") (name "unconnected-(AB20-PadBE1)") (class "Default")
      (node (ref "AB20") (pin "BE1") (pinfunction "BE1_BE1") (pintype "output"))
    )
    (net (code "287") (name "unconnected-(AB20-PadBU2)") (class "Default")
      (node (ref "AB20") (pin "BU2") (pinfunction "BU2_BU2") (pintype "output"))
    )
    (net (code "288") (name "unconnected-(AB20-PadBV2)") (class "Default")
      (node (ref "AB20") (pin "BV2") (pinfunction "BV2_BV2") (pintype "open_collector"))
    )
    (net (code "289") (name "unconnected-(AB20O-OUT-PadBM1)") (class "Default")
      (node (ref "AB20") (pin "BM1") (pinfunction "OUT_BM1") (pintype "output"))
    )
    (net (code "290") (name "unconnected-(AB20P-OUT-PadBF1)") (class "Default")
      (node (ref "AB20") (pin "BF1") (pinfunction "OUT_BF1") (pintype "output"))
    )
  )
)
